# EEZ_DIB_AFE3_r1B4.net
KiCad netlist of a schematic drawn in EAGLE
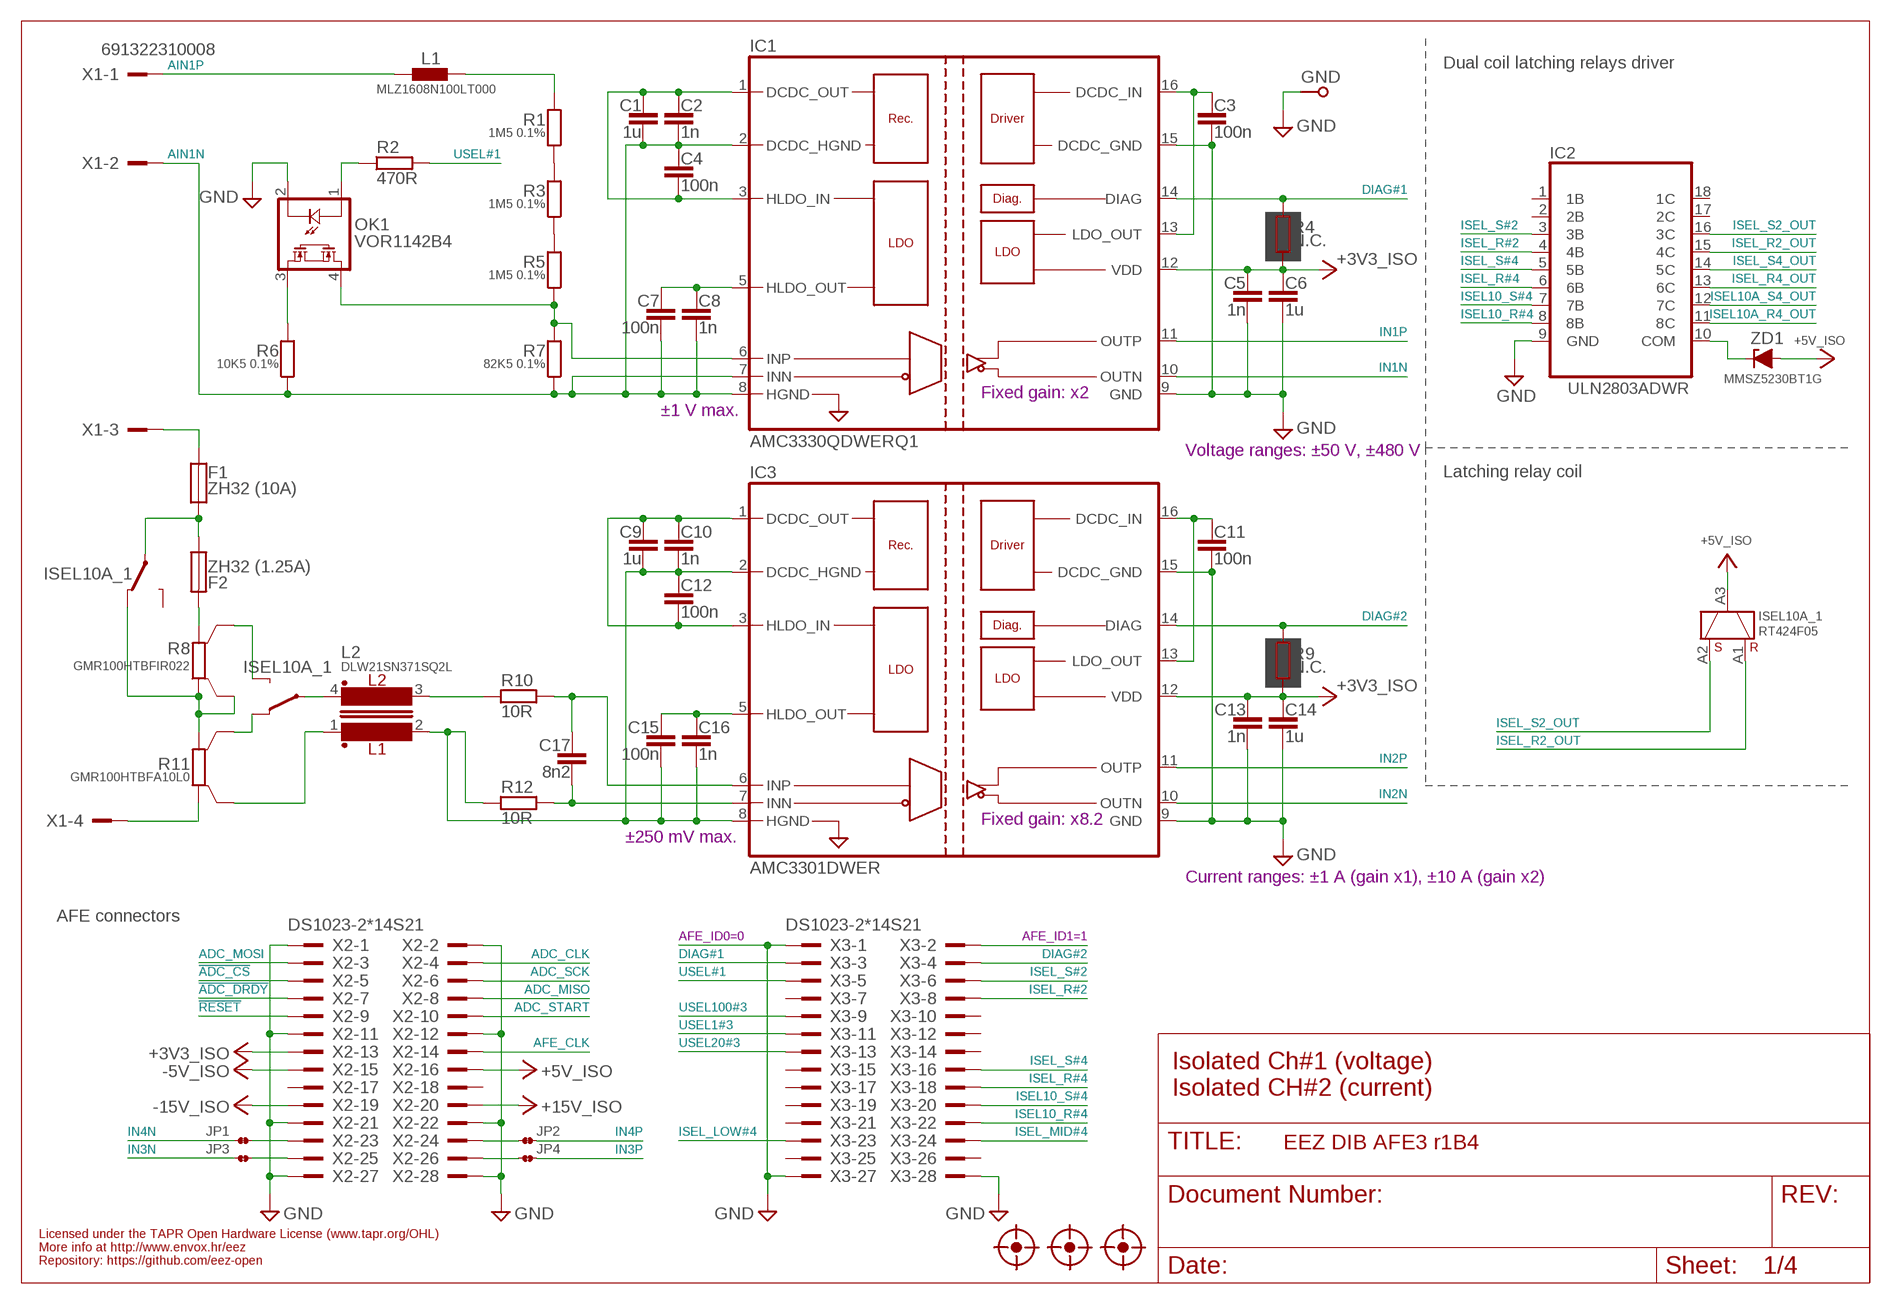
[diagram p0: schematic, sheet 1]
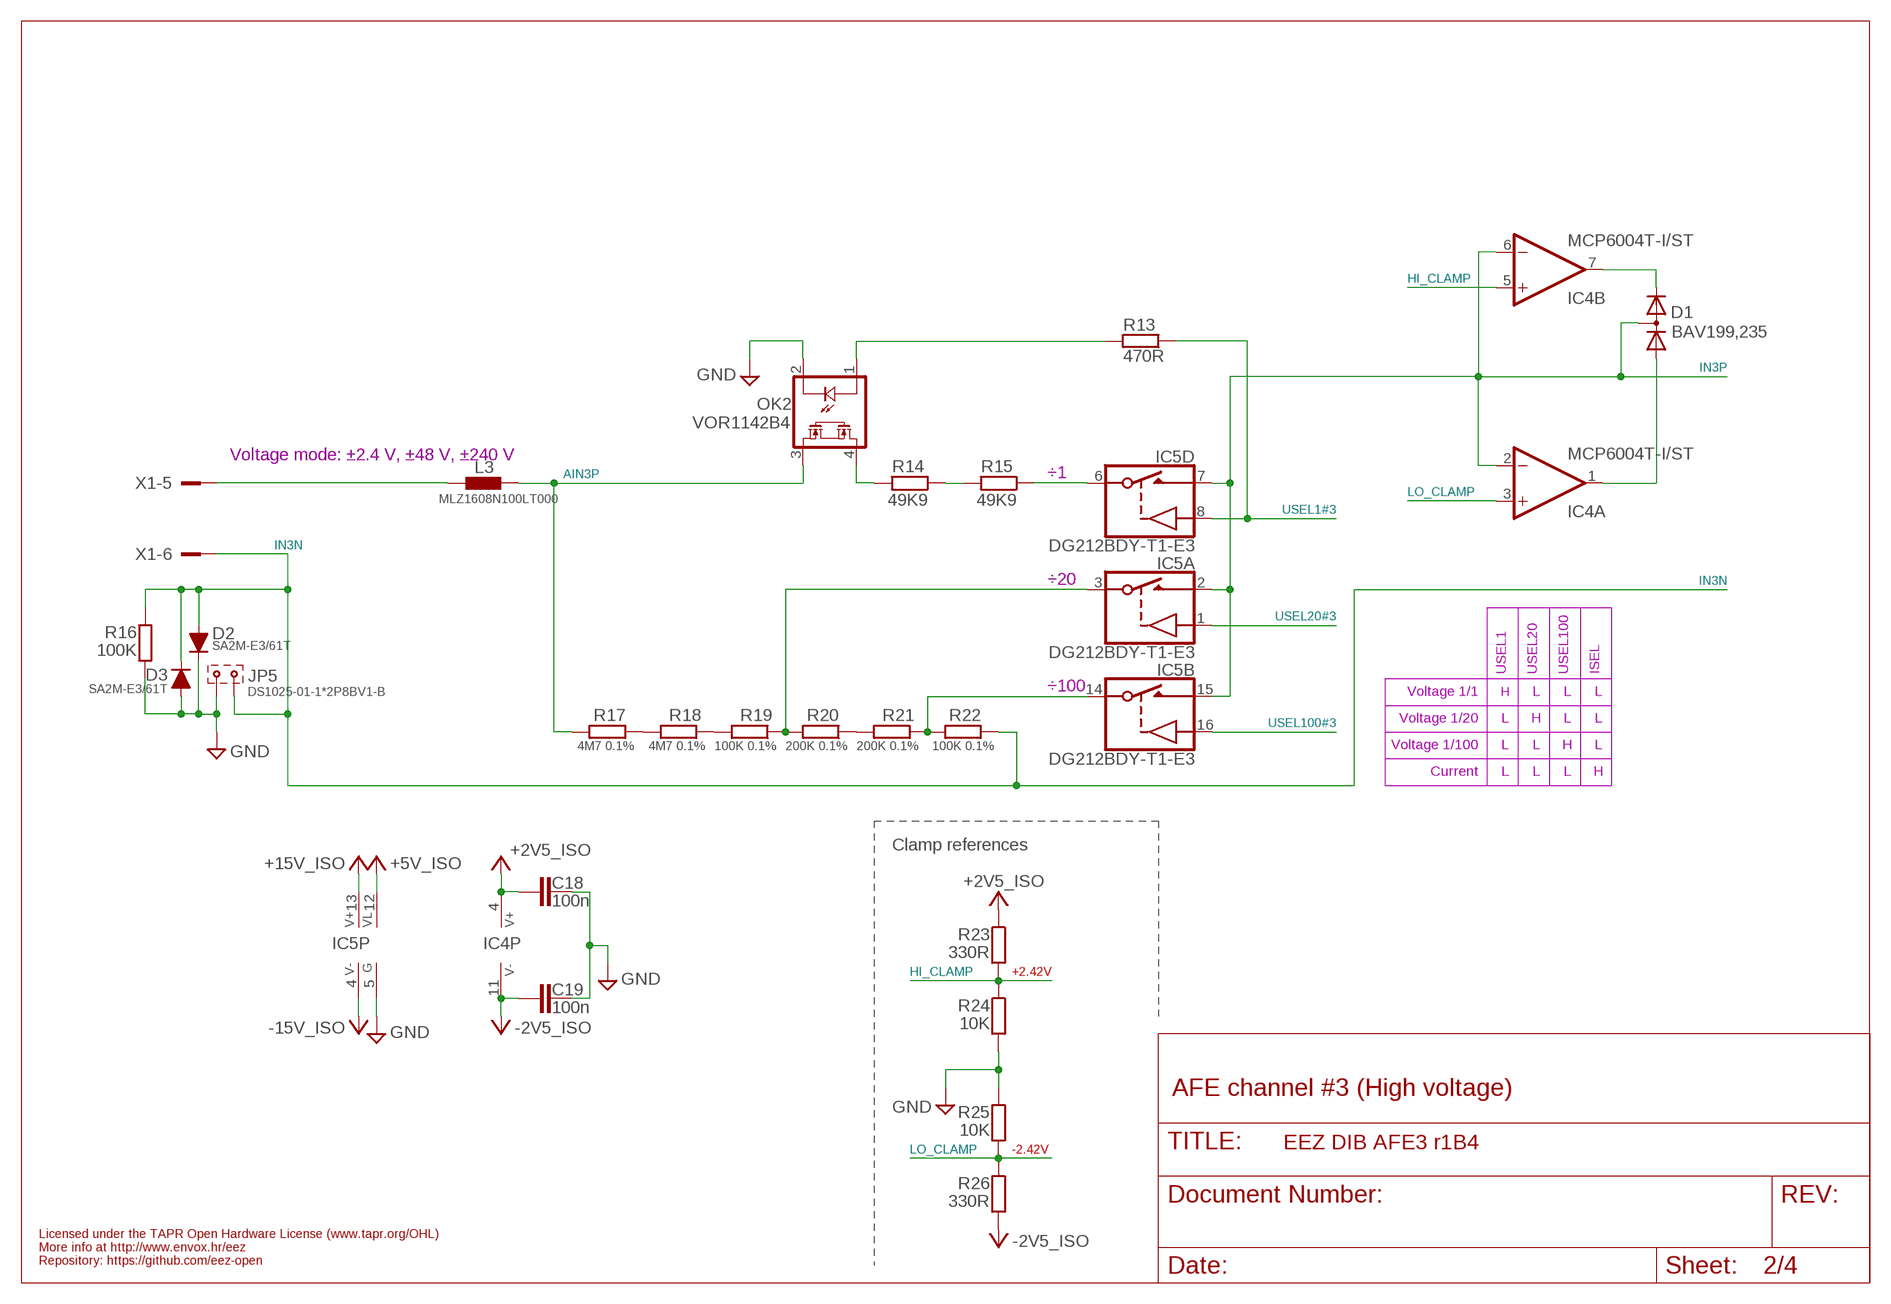
[diagram p1: schematic, sheet 2]
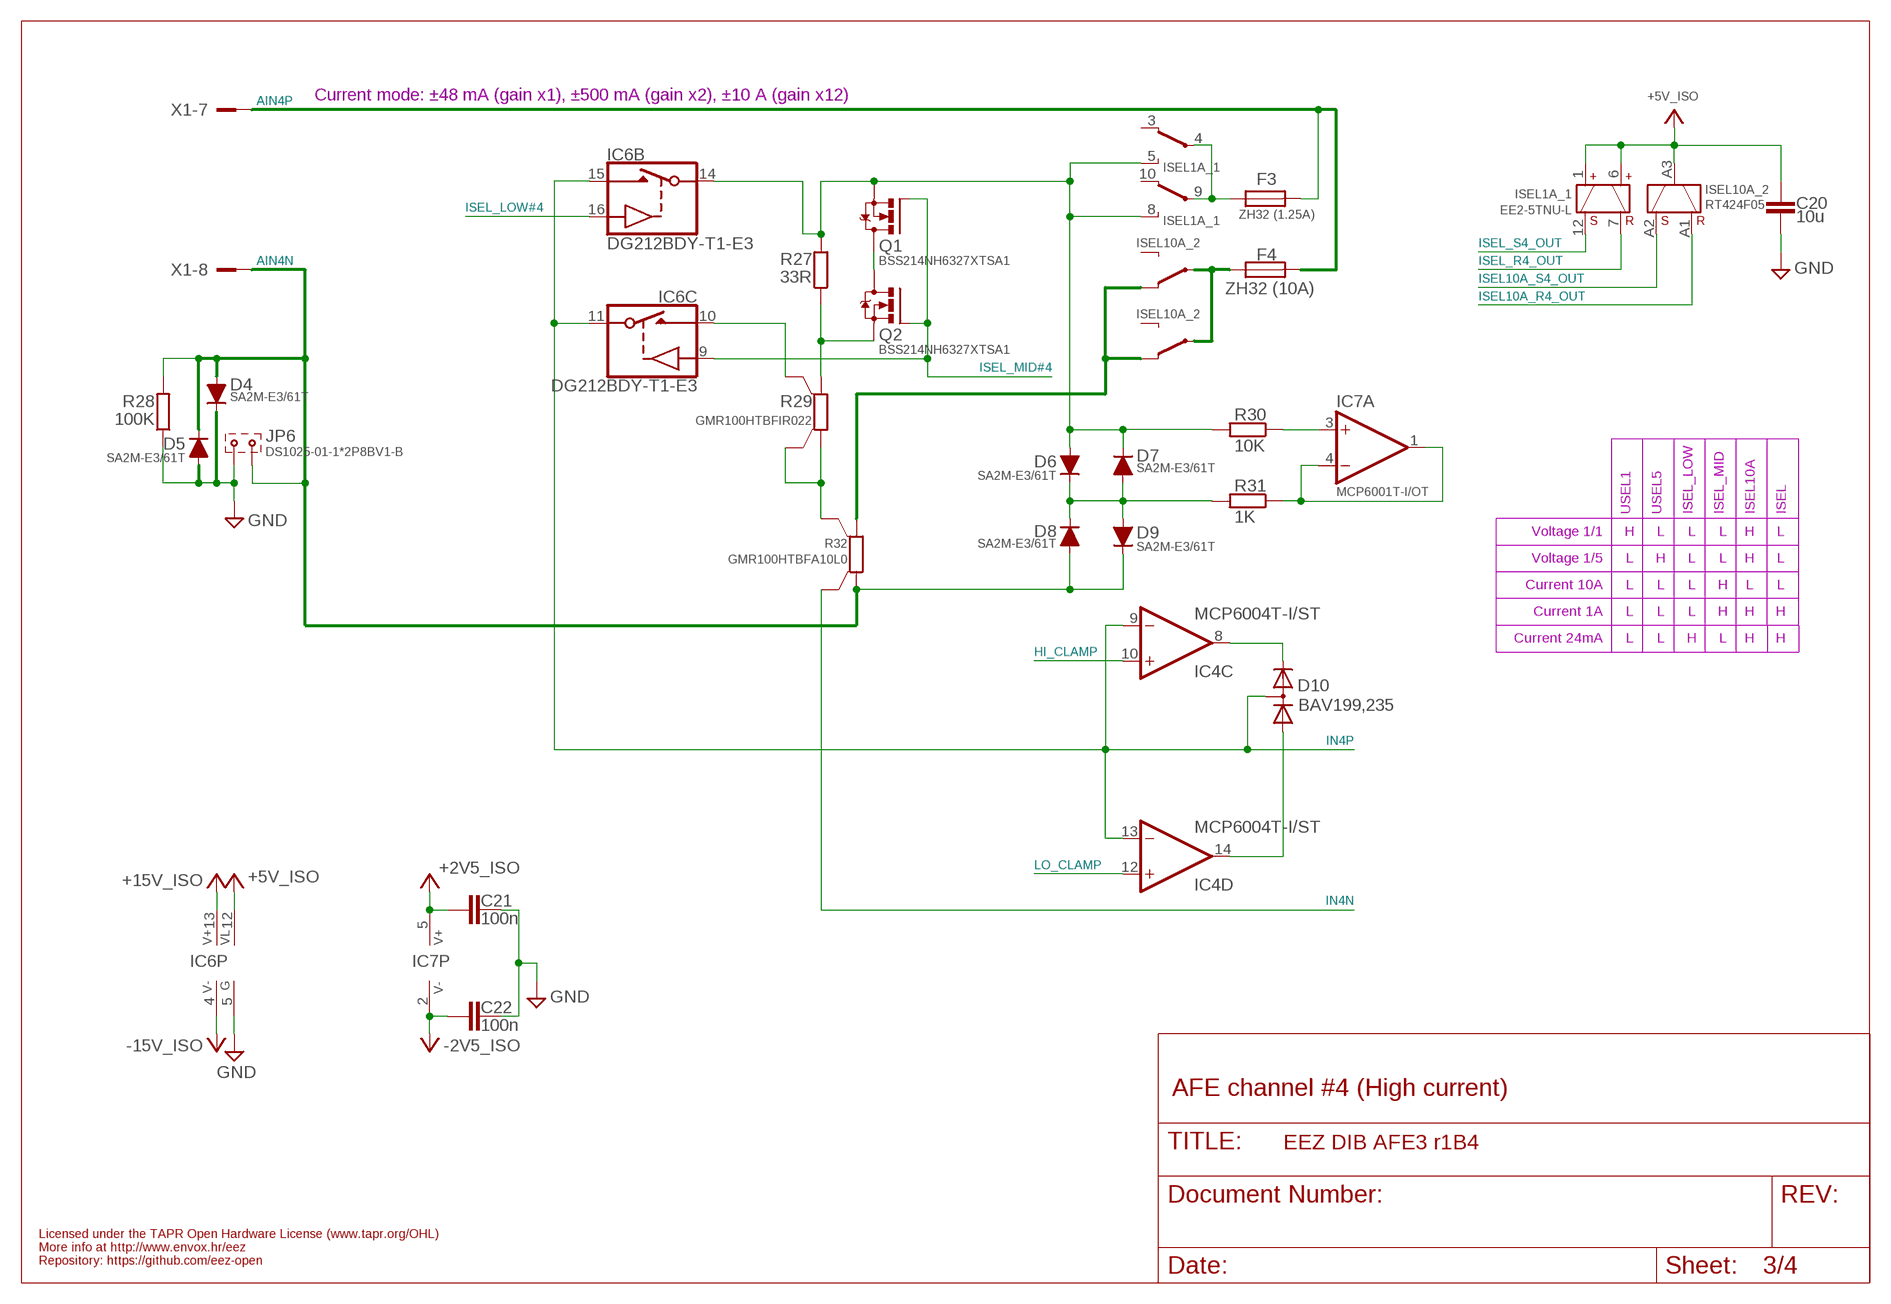
[diagram p2: schematic, sheet 3]
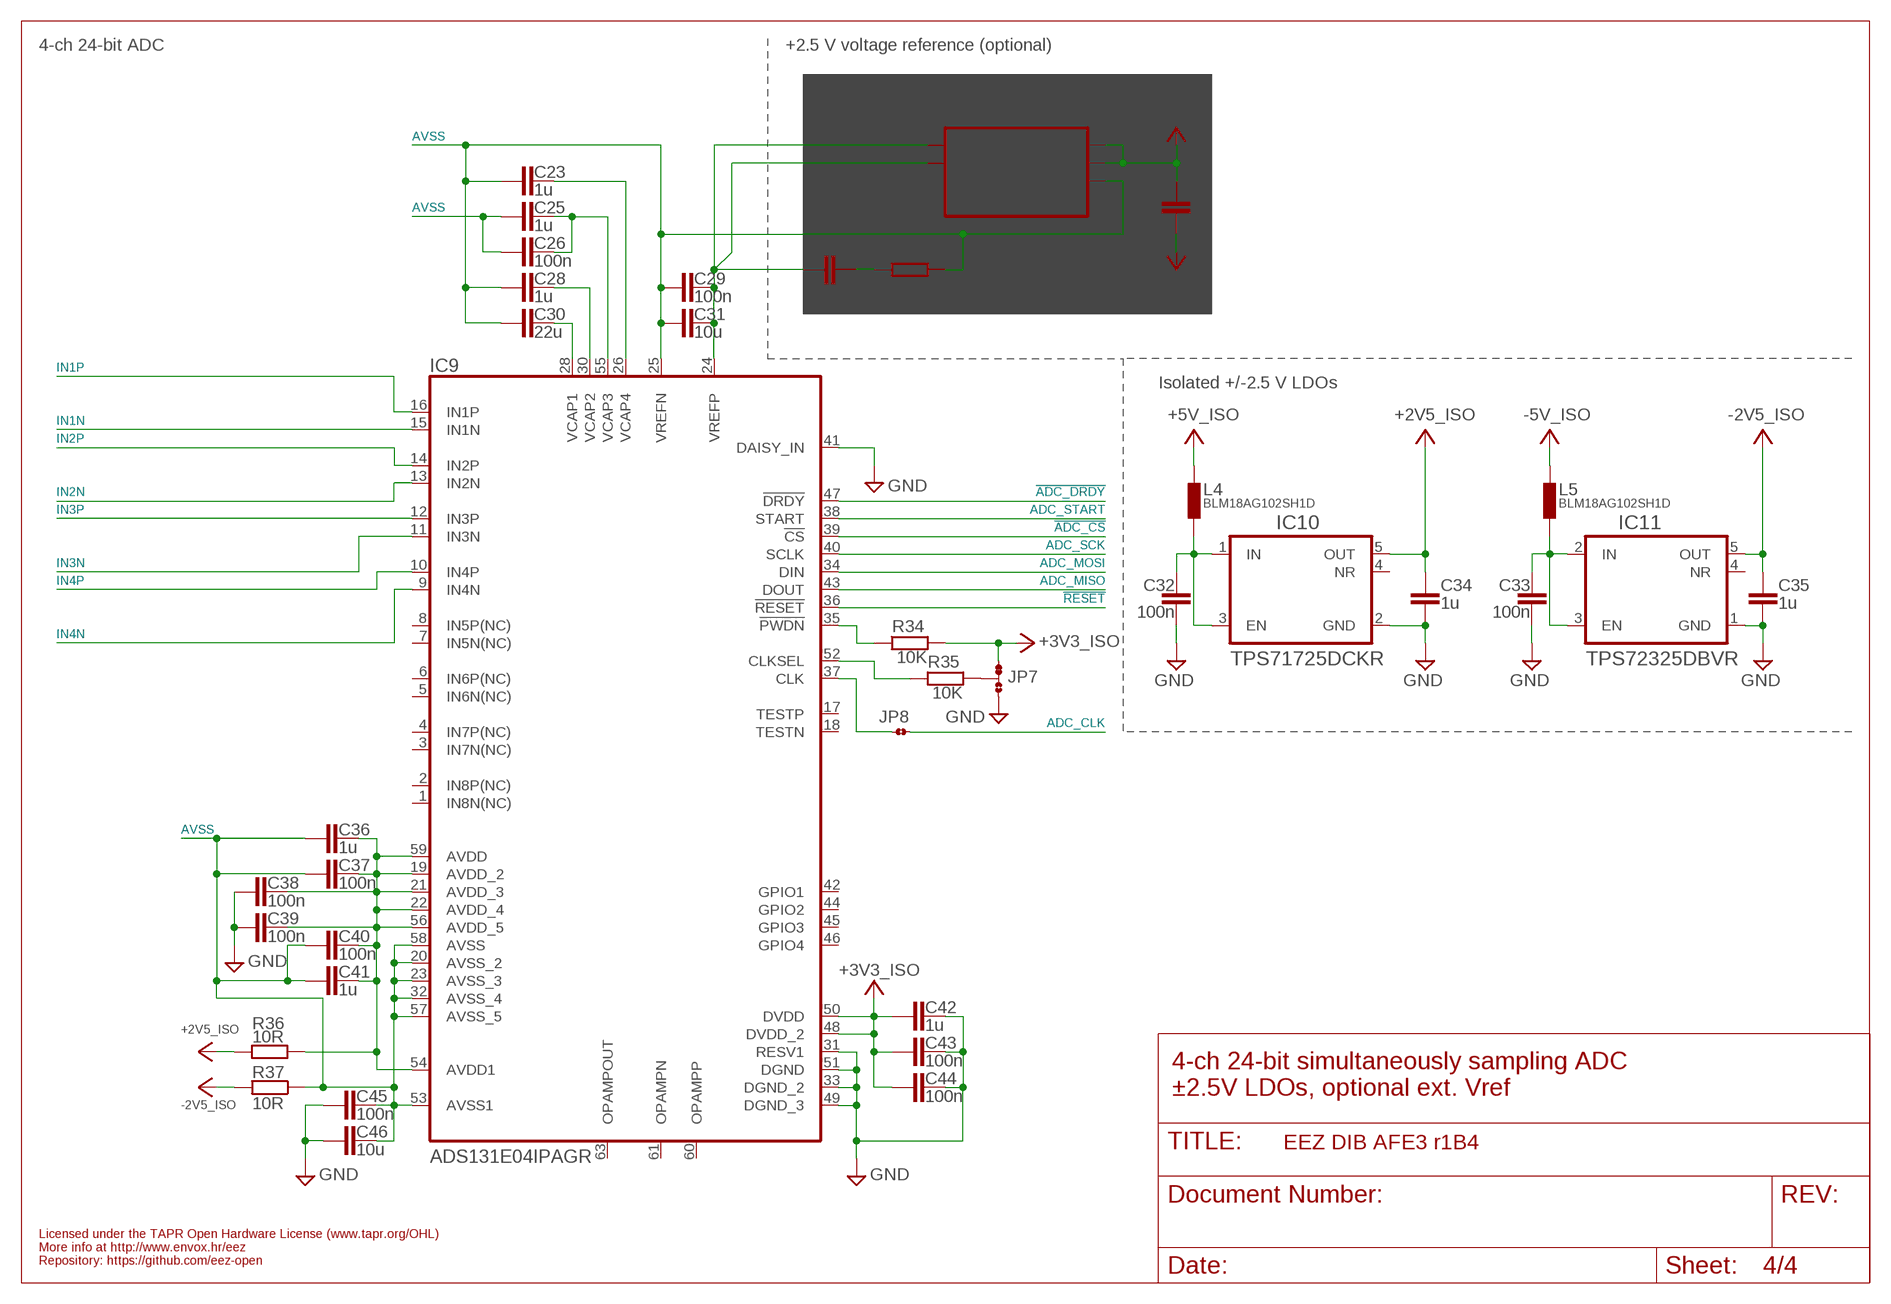
[diagram p3: schematic, sheet 4]

(export (version "E")
  (design (tool "Eeschema 10.0.6"))
  (components
    (comp (ref "C20")
      (value "10u")
      (footprint "eagle-import:C1206")
      (libsource (lib "eagle-import") (part "C-EUC1206"))
    )
    (comp (ref "C21")
      (value "100n")
      (footprint "eagle-import:C0603")
      (libsource (lib "eagle-import") (part "C-EUC0603"))
    )
    (comp (ref "C22")
      (value "100n")
      (footprint "eagle-import:C0603")
      (libsource (lib "eagle-import") (part "C-EUC0603"))
    )
    (comp (ref "D4")
      (value "SA2M-E3/61T")
      (footprint "eagle-import:SMA_NARROW")
      (libsource (lib "eagle-import") (part "DIODE_SMA-NARROW"))
    )
    (comp (ref "D5")
      (value "SA2M-E3/61T")
      (footprint "eagle-import:SMA_NARROW")
      (libsource (lib "eagle-import") (part "DIODE_SMA-NARROW"))
    )
    (comp (ref "D6")
      (value "SA2M-E3/61T")
      (footprint "eagle-import:SMA_NARROW")
      (libsource (lib "eagle-import") (part "DIODE_SMA-NARROW"))
    )
    (comp (ref "D7")
      (value "SA2M-E3/61T")
      (footprint "eagle-import:SMA_NARROW")
      (libsource (lib "eagle-import") (part "DIODE_SMA-NARROW"))
    )
    (comp (ref "D8")
      (value "SA2M-E3/61T")
      (footprint "eagle-import:SMA_NARROW")
      (libsource (lib "eagle-import") (part "DIODE_SMA-NARROW"))
    )
    (comp (ref "D9")
      (value "SA2M-E3/61T")
      (footprint "eagle-import:SMA_NARROW")
      (libsource (lib "eagle-import") (part "DIODE_SMA-NARROW"))
    )
    (comp (ref "D10")
      (value "BAV199,235")
      (footprint "eagle-import:SOT23")
      (libsource (lib "eagle-import") (part "BAV199"))
    )
    (comp (ref "F3")
      (value "ZH32 (1.25A)")
      (footprint "eagle-import:ZH32")
      (libsource (lib "eagle-import") (part "ZH32"))
    )
    (comp (ref "F4")
      (value "ZH32 (10A)")
      (footprint "eagle-import:ZH32")
      (libsource (lib "eagle-import") (part "ZH32"))
    )
    (comp (ref "IC4")
      (value "MCP6004T-I/ST")
      (footprint "eagle-import:PW(R-PDSO-G14)")
      (libsource (lib "eagle-import") (part "OPA4197PW"))
    )
    (comp (ref "IC6")
      (value "DG212BDY-T1-E3")
      (footprint "eagle-import:SO16")
      (libsource (lib "eagle-import") (part "DG212BDY-T1-E3"))
    )
    (comp (ref "IC7")
      (value "MCP6001T-I/OT")
      (footprint "eagle-import:DBV5")
      (libsource (lib "eagle-import") (part "OPA376AIDBVR"))
    )
    (comp (ref "ISEL1A_1")
      (value "EE2-5TNU-L")
      (footprint "eagle-import:G6SK-2F")
      (libsource (lib "eagle-import") (part "G6SK-2F"))
    )
    (comp (ref "ISEL10A_2")
      (value "RT424F05")
      (footprint "eagle-import:RT424FXX")
      (libsource (lib "eagle-import") (part "RT424FXX"))
    )
    (comp (ref "JP6")
      (value "DS1025-01-1*2P8BV1-B")
      (footprint "eagle-import:2MM-2")
      (libsource (lib "eagle-import") (part "JUMPER-2PIN-2MM"))
    )
    (comp (ref "Q1")
      (value "BSS214NH6327XTSA1")
      (footprint "eagle-import:SOT103P240X110-3N")
      (fields
        (field (name "MPN") "2N7002-7-F")
        (field (name "MPN_1") "2N7002-7-F")
        (field (name "OC_FARNELL") "1713823")
        (field (name "OC_NEWARK") "25R5679")
        (field (name "PACKAGE") "SOT-23-3")
        (field (name "SUPPLIER") "DIODES INC.")
      )
      (libsource (lib "eagle-import") (part "2N7002"))
    )
    (comp (ref "Q2")
      (value "BSS214NH6327XTSA1")
      (footprint "eagle-import:SOT103P240X110-3N")
      (fields (field (name "MPN") "2N7002-7-F"))
      (libsource (lib "eagle-import") (part "2N7002"))
    )
    (comp (ref "R27")
      (value "33R")
      (footprint "eagle-import:R1206")
      (libsource (lib "eagle-import") (part "R-EU_R1206"))
    )
    (comp (ref "R28")
      (value "100K")
      (footprint "eagle-import:R1206")
      (libsource (lib "eagle-import") (part "R-EU_R1206"))
    )
    (comp (ref "R29")
      (value "GMR100HTBFIR022")
      (footprint "eagle-import:R_2512-4WIRE")
      (libsource (lib "eagle-import") (part "R-EU_4WIRE2512"))
    )
    (comp (ref "R30")
      (value "10K")
      (footprint "eagle-import:R0805")
      (libsource (lib "eagle-import") (part "R-EU_R0805"))
    )
    (comp (ref "R31")
      (value "1K")
      (footprint "eagle-import:R0805")
      (libsource (lib "eagle-import") (part "R-EU_R0805"))
    )
    (comp (ref "R32")
      (value "GMR100HTBFA10L0")
      (footprint "eagle-import:R_2512-4WIRE")
      (libsource (lib "eagle-import") (part "R-EU_4WIRE2512"))
    )
    (comp (ref "X1")
      (value "691322310008")
      (footprint "eagle-import:691322310008")
      (libsource (lib "eagle-import") (part "691322310008"))
    )
    (comp (ref "C1")
      (value "1u")
      (footprint "eagle-import:C0603")
      (libsource (lib "eagle-import") (part "C-EUC0603"))
    )
    (comp (ref "C2")
      (value "1n")
      (footprint "eagle-import:C0603")
      (libsource (lib "eagle-import") (part "C-EUC0603"))
    )
    (comp (ref "C3")
      (value "100n")
      (footprint "eagle-import:C0603")
      (libsource (lib "eagle-import") (part "C-EUC0603"))
    )
    (comp (ref "C4")
      (value "100n")
      (footprint "eagle-import:C0603")
      (libsource (lib "eagle-import") (part "C-EUC0603"))
    )
    (comp (ref "C5")
      (value "1n")
      (footprint "eagle-import:C1206")
      (libsource (lib "eagle-import") (part "C-EUC1206"))
    )
    (comp (ref "C6")
      (value "1u")
      (footprint "eagle-import:C1206")
      (libsource (lib "eagle-import") (part "C-EUC1206"))
    )
    (comp (ref "C7")
      (value "100n")
      (footprint "eagle-import:C1206")
      (libsource (lib "eagle-import") (part "C-EUC1206"))
    )
    (comp (ref "C8")
      (value "1n")
      (footprint "eagle-import:C1206")
      (libsource (lib "eagle-import") (part "C-EUC1206"))
    )
    (comp (ref "C9")
      (value "1u")
      (footprint "eagle-import:C0603")
      (libsource (lib "eagle-import") (part "C-EUC0603"))
    )
    (comp (ref "C10")
      (value "1n")
      (footprint "eagle-import:C0603")
      (libsource (lib "eagle-import") (part "C-EUC0603"))
    )
    (comp (ref "C11")
      (value "100n")
      (footprint "eagle-import:C0603")
      (libsource (lib "eagle-import") (part "C-EUC0603"))
    )
    (comp (ref "C12")
      (value "100n")
      (footprint "eagle-import:C0603")
      (libsource (lib "eagle-import") (part "C-EUC0603"))
    )
    (comp (ref "C13")
      (value "1n")
      (footprint "eagle-import:C1206")
      (libsource (lib "eagle-import") (part "C-EUC1206"))
    )
    (comp (ref "C14")
      (value "1u")
      (footprint "eagle-import:C1206")
      (libsource (lib "eagle-import") (part "C-EUC1206"))
    )
    (comp (ref "C15")
      (value "100n")
      (footprint "eagle-import:C1206")
      (libsource (lib "eagle-import") (part "C-EUC1206"))
    )
    (comp (ref "C16")
      (value "1n")
      (footprint "eagle-import:C1206")
      (libsource (lib "eagle-import") (part "C-EUC1206"))
    )
    (comp (ref "C17")
      (value "8n2")
      (footprint "eagle-import:C0603")
      (libsource (lib "eagle-import") (part "C-EUC0603"))
    )
    (comp (ref "F1")
      (value "ZH32 (10A)")
      (footprint "eagle-import:ZH32")
      (libsource (lib "eagle-import") (part "ZH32"))
    )
    (comp (ref "F2")
      (value "ZH32 (1.25A)")
      (footprint "eagle-import:ZH32")
      (libsource (lib "eagle-import") (part "ZH32"))
    )
    (comp (ref "FM1")
      (value "FIDUCIAL_2")
      (footprint "eagle-import:FIDUCIAL_DUAL")
      (libsource (lib "eagle-import") (part "FIDUCIAL_2"))
    )
    (comp (ref "FM2")
      (value "FIDUCIAL_2")
      (footprint "eagle-import:FIDUCIAL_DUAL")
      (libsource (lib "eagle-import") (part "FIDUCIAL_2"))
    )
    (comp (ref "FM3")
      (value "FIDUCIAL_2")
      (footprint "eagle-import:FIDUCIAL_DUAL")
      (libsource (lib "eagle-import") (part "FIDUCIAL_2"))
    )
    (comp (ref "GND")
      (value "PCB_TEST_TABSHIELD")
      (footprint "eagle-import:PCB_SHIELD_TAB")
      (libsource (lib "eagle-import") (part "PCB_TEST_TABSHIELD"))
    )
    (comp (ref "IC1")
      (value "AMC3330QDWERQ1")
      (footprint "eagle-import:DW16")
      (libsource (lib "eagle-import") (part "AMC3301DWER"))
    )
    (comp (ref "IC2")
      (value "ULN2803ADWR")
      (footprint "eagle-import:DW18_TEX-M")
      (libsource (lib "eagle-import") (part "ULN2803ADWR"))
    )
    (comp (ref "IC3")
      (value "AMC3301DWER")
      (footprint "eagle-import:DW16")
      (libsource (lib "eagle-import") (part "AMC3301DWER"))
    )
    (comp (ref "ISEL10A_1")
      (value "RT424F05")
      (footprint "eagle-import:RT424FXX")
      (libsource (lib "eagle-import") (part "RT424FXX"))
    )
    (comp (ref "JP1")
      (value "JP2-NOCUT-0805")
      (footprint "eagle-import:JP2-0805-NOCUT")
      (libsource (lib "eagle-import") (part "JP2-NOCUT-0805"))
    )
    (comp (ref "JP2")
      (value "JP2-NOCUT-0805")
      (footprint "eagle-import:JP2-0805-NOCUT")
      (libsource (lib "eagle-import") (part "JP2-NOCUT-0805"))
    )
    (comp (ref "JP3")
      (value "JP2-NOCUT-0805")
      (footprint "eagle-import:JP2-0805-NOCUT")
      (libsource (lib "eagle-import") (part "JP2-NOCUT-0805"))
    )
    (comp (ref "JP4")
      (value "JP2-NOCUT-0805")
      (footprint "eagle-import:JP2-0805-NOCUT")
      (libsource (lib "eagle-import") (part "JP2-NOCUT-0805"))
    )
    (comp (ref "L1")
      (value "MLZ1608N100LT000")
      (footprint "eagle-import:BEAD0603")
      (libsource (lib "eagle-import") (part "FERRITE_BEAD0603"))
    )
    (comp (ref "L2")
      (value "DLW21SN371SQ2L")
      (footprint "eagle-import:MURATA_DLW21S")
      (libsource (lib "eagle-import") (part "DLW21S"))
    )
    (comp (ref "OK1")
      (value "VOR1142B4")
      (footprint "eagle-import:DIL4-SMD")
      (libsource (lib "eagle-import") (part "VOR1142B4"))
    )
    (comp (ref "R1")
      (value "1M5 0.1%")
      (footprint "eagle-import:R1206")
      (libsource (lib "eagle-import") (part "R-EU_R1206"))
    )
    (comp (ref "R2")
      (value "470R")
      (footprint "eagle-import:R0805")
      (libsource (lib "eagle-import") (part "R-EU_R0805"))
    )
    (comp (ref "R3")
      (value "1M5 0.1%")
      (footprint "eagle-import:R1206")
      (libsource (lib "eagle-import") (part "R-EU_R1206"))
    )
    (comp (ref "R4")
      (value "N.C.")
      (footprint "eagle-import:R0805")
      (libsource (lib "eagle-import") (part "R-EU_R0805"))
    )
    (comp (ref "R5")
      (value "1M5 0.1%")
      (footprint "eagle-import:R1206")
      (libsource (lib "eagle-import") (part "R-EU_R1206"))
    )
    (comp (ref "R6")
      (value "10K5 0.1%")
      (footprint "eagle-import:R1206")
      (libsource (lib "eagle-import") (part "R-EU_R1206"))
    )
    (comp (ref "R7")
      (value "82K5 0.1%")
      (footprint "eagle-import:R1206")
      (libsource (lib "eagle-import") (part "R-EU_R1206"))
    )
    (comp (ref "R8")
      (value "GMR100HTBFIR022")
      (footprint "eagle-import:R_2512-4WIRE")
      (libsource (lib "eagle-import") (part "R-EU_4WIRE2512"))
    )
    (comp (ref "R9")
      (value "N.C.")
      (footprint "eagle-import:R0805")
      (libsource (lib "eagle-import") (part "R-EU_R0805"))
    )
    (comp (ref "R10")
      (value "10R")
      (footprint "eagle-import:R0805")
      (libsource (lib "eagle-import") (part "R-EU_R0805"))
    )
    (comp (ref "R11")
      (value "GMR100HTBFA10L0")
      (footprint "eagle-import:R_2512-4WIRE")
      (libsource (lib "eagle-import") (part "R-EU_4WIRE2512"))
    )
    (comp (ref "R12")
      (value "10R")
      (footprint "eagle-import:R0805")
      (libsource (lib "eagle-import") (part "R-EU_R0805"))
    )
    (comp (ref "X2")
      (value "DS1023-2*14S21")
      (footprint "eagle-import:TSW-114-07-F-D")
      (libsource (lib "eagle-import") (part "TSW-114-07-F-D"))
    )
    (comp (ref "X3")
      (value "DS1023-2*14S21")
      (footprint "eagle-import:TSW-114-07-F-D")
      (libsource (lib "eagle-import") (part "TSW-114-07-F-D"))
    )
    (comp (ref "ZD1")
      (value "MMSZ5230BT1G")
      (footprint "eagle-import:SOD123")
      (libsource (lib "eagle-import") (part "ZENER-DIODESOD123"))
    )
    (comp (ref "C23")
      (value "1u")
      (footprint "eagle-import:C0805")
      (libsource (lib "eagle-import") (part "C-EUC0805"))
    )
    (comp (ref "C24")
      (value "N.C.")
      (footprint "eagle-import:C1206")
      (libsource (lib "eagle-import") (part "C-EUC1206"))
    )
    (comp (ref "C25")
      (value "1u")
      (footprint "eagle-import:C0805")
      (libsource (lib "eagle-import") (part "C-EUC0805"))
    )
    (comp (ref "C26")
      (value "100n")
      (footprint "eagle-import:C0603")
      (libsource (lib "eagle-import") (part "C-EUC0603"))
    )
    (comp (ref "C27")
      (value "N.C.")
      (footprint "eagle-import:C1206")
      (libsource (lib "eagle-import") (part "C-EUC1206"))
    )
    (comp (ref "C28")
      (value "1u")
      (footprint "eagle-import:C0805")
      (libsource (lib "eagle-import") (part "C-EUC0805"))
    )
    (comp (ref "C29")
      (value "100n")
      (footprint "eagle-import:C0603")
      (libsource (lib "eagle-import") (part "C-EUC0603"))
    )
    (comp (ref "C30")
      (value "22u")
      (footprint "eagle-import:C1206")
      (libsource (lib "eagle-import") (part "C-EUC1206"))
    )
    (comp (ref "C31")
      (value "10u")
      (footprint "eagle-import:C1206")
      (libsource (lib "eagle-import") (part "C-EUC1206"))
    )
    (comp (ref "C32")
      (value "100n")
      (footprint "eagle-import:C0603")
      (libsource (lib "eagle-import") (part "C-EUC0603"))
    )
    (comp (ref "C33")
      (value "100n")
      (footprint "eagle-import:C0603")
      (libsource (lib "eagle-import") (part "C-EUC0603"))
    )
    (comp (ref "C34")
      (value "1u")
      (footprint "eagle-import:C0805")
      (libsource (lib "eagle-import") (part "C-EUC0805"))
    )
    (comp (ref "C35")
      (value "1u")
      (footprint "eagle-import:C0805")
      (libsource (lib "eagle-import") (part "C-EUC0805"))
    )
    (comp (ref "C36")
      (value "1u")
      (footprint "eagle-import:C0805")
      (libsource (lib "eagle-import") (part "C-EUC0805"))
    )
    (comp (ref "C37")
      (value "100n")
      (footprint "eagle-import:C0603")
      (libsource (lib "eagle-import") (part "C-EUC0603"))
    )
    (comp (ref "C38")
      (value "100n")
      (footprint "eagle-import:C0603")
      (libsource (lib "eagle-import") (part "C-EUC0603"))
    )
    (comp (ref "C39")
      (value "100n")
      (footprint "eagle-import:C0603")
      (libsource (lib "eagle-import") (part "C-EUC0603"))
    )
    (comp (ref "C40")
      (value "100n")
      (footprint "eagle-import:C0603")
      (libsource (lib "eagle-import") (part "C-EUC0603"))
    )
    (comp (ref "C41")
      (value "1u")
      (footprint "eagle-import:C0805")
      (libsource (lib "eagle-import") (part "C-EUC0805"))
    )
    (comp (ref "C42")
      (value "1u")
      (footprint "eagle-import:C0805")
      (libsource (lib "eagle-import") (part "C-EUC0805"))
    )
    (comp (ref "C43")
      (value "100n")
      (footprint "eagle-import:C0603")
      (libsource (lib "eagle-import") (part "C-EUC0603"))
    )
    (comp (ref "C44")
      (value "100n")
      (footprint "eagle-import:C0603")
      (libsource (lib "eagle-import") (part "C-EUC0603"))
    )
    (comp (ref "C45")
      (value "100n")
      (footprint "eagle-import:C0603")
      (libsource (lib "eagle-import") (part "C-EUC0603"))
    )
    (comp (ref "C46")
      (value "10u")
      (footprint "eagle-import:C1206")
      (libsource (lib "eagle-import") (part "C-EUC1206"))
    )
    (comp (ref "IC8")
      (value "N.C.")
      (footprint "eagle-import:MSOP-8_MS_LIT")
      (libsource (lib "eagle-import") (part "LTC6655BHMS8"))
    )
    (comp (ref "IC9")
      (value "ADS131E04IPAGR")
      (footprint "eagle-import:PAG64")
      (libsource (lib "eagle-import") (part "ADS131E0XIPAG"))
    )
    (comp (ref "IC10")
      (value "TPS71725DCKR")
      (footprint "eagle-import:DCK5")
      (libsource (lib "eagle-import") (part "TPS71725DCKR"))
    )
    (comp (ref "IC11")
      (value "TPS72325DBVR")
      (footprint "eagle-import:DBV5")
      (libsource (lib "eagle-import") (part "TPS72325DBVR"))
    )
    (comp (ref "JP7")
      (value "JP3-CUT-0805-ROTATED")
      (footprint "eagle-import:JP3-0805-CUT2")
      (libsource (lib "eagle-import") (part "JP3-CUT-0805-ROTATED"))
    )
    (comp (ref "JP8")
      (value "JP2-CUT-0805")
      (footprint "eagle-import:R_0805")
      (libsource (lib "eagle-import") (part "JP2-CUT-0805"))
    )
    (comp (ref "L4")
      (value "BLM18AG102SH1D")
      (footprint "eagle-import:BEAD0603")
      (libsource (lib "eagle-import") (part "FERRITE_BEAD0603"))
    )
    (comp (ref "L5")
      (value "BLM18AG102SH1D")
      (footprint "eagle-import:BEAD0603")
      (libsource (lib "eagle-import") (part "FERRITE_BEAD0603"))
    )
    (comp (ref "R33")
      (value "N.C.")
      (footprint "eagle-import:R0805")
      (libsource (lib "eagle-import") (part "R-EU_R0805"))
    )
    (comp (ref "R34")
      (value "10K")
      (footprint "eagle-import:R0805")
      (libsource (lib "eagle-import") (part "R-EU_R0805"))
    )
    (comp (ref "R35")
      (value "10K")
      (footprint "eagle-import:R0805")
      (libsource (lib "eagle-import") (part "R-EU_R0805"))
    )
    (comp (ref "R36")
      (value "10R")
      (footprint "eagle-import:R0805")
      (libsource (lib "eagle-import") (part "R-EU_R0805"))
    )
    (comp (ref "R37")
      (value "10R")
      (footprint "eagle-import:R0805")
      (libsource (lib "eagle-import") (part "R-EU_R0805"))
    )
    (comp (ref "C18")
      (value "100n")
      (footprint "eagle-import:C0603")
      (libsource (lib "eagle-import") (part "C-EUC0603"))
    )
    (comp (ref "C19")
      (value "100n")
      (footprint "eagle-import:C0603")
      (libsource (lib "eagle-import") (part "C-EUC0603"))
    )
    (comp (ref "D1")
      (value "BAV199,235")
      (footprint "eagle-import:SOT23")
      (libsource (lib "eagle-import") (part "BAV199"))
    )
    (comp (ref "D2")
      (value "SA2M-E3/61T")
      (footprint "eagle-import:SMA_NARROW")
      (libsource (lib "eagle-import") (part "DIODE_SMA-NARROW"))
    )
    (comp (ref "D3")
      (value "SA2M-E3/61T")
      (footprint "eagle-import:SMA_NARROW")
      (libsource (lib "eagle-import") (part "DIODE_SMA-NARROW"))
    )
    (comp (ref "IC5")
      (value "DG212BDY-T1-E3")
      (footprint "eagle-import:SO16")
      (libsource (lib "eagle-import") (part "DG212BDY-T1-E3"))
    )
    (comp (ref "JP5")
      (value "DS1025-01-1*2P8BV1-B")
      (footprint "eagle-import:2MM-2")
      (libsource (lib "eagle-import") (part "JUMPER-2PIN-2MM"))
    )
    (comp (ref "L3")
      (value "MLZ1608N100LT000")
      (footprint "eagle-import:BEAD0603")
      (libsource (lib "eagle-import") (part "FERRITE_BEAD0603"))
    )
    (comp (ref "OK2")
      (value "VOR1142B4")
      (footprint "eagle-import:DIL4-SMD")
      (libsource (lib "eagle-import") (part "VOR1142B4"))
    )
    (comp (ref "R13")
      (value "470R")
      (footprint "eagle-import:R0805")
      (libsource (lib "eagle-import") (part "R-EU_R0805"))
    )
    (comp (ref "R14")
      (value "49K9")
      (footprint "eagle-import:R1206")
      (libsource (lib "eagle-import") (part "R-EU_R1206"))
    )
    (comp (ref "R15")
      (value "49K9")
      (footprint "eagle-import:R1206")
      (libsource (lib "eagle-import") (part "R-EU_R1206"))
    )
    (comp (ref "R16")
      (value "100K")
      (footprint "eagle-import:R1206")
      (libsource (lib "eagle-import") (part "R-EU_R1206"))
    )
    (comp (ref "R17")
      (value "4M7 0.1%")
      (footprint "eagle-import:R1206")
      (libsource (lib "eagle-import") (part "R-EU_R1206"))
    )
    (comp (ref "R18")
      (value "4M7 0.1%")
      (footprint "eagle-import:R1206")
      (libsource (lib "eagle-import") (part "R-EU_R1206"))
    )
    (comp (ref "R19")
      (value "100K 0.1%")
      (footprint "eagle-import:R1206")
      (libsource (lib "eagle-import") (part "R-EU_R1206"))
    )
    (comp (ref "R20")
      (value "200K 0.1%")
      (footprint "eagle-import:R1206")
      (libsource (lib "eagle-import") (part "R-EU_R1206"))
    )
    (comp (ref "R21")
      (value "200K 0.1%")
      (footprint "eagle-import:R1206")
      (libsource (lib "eagle-import") (part "R-EU_R1206"))
    )
    (comp (ref "R22")
      (value "100K 0.1%")
      (footprint "eagle-import:R1206")
      (libsource (lib "eagle-import") (part "R-EU_R1206"))
    )
    (comp (ref "R23")
      (value "330R")
      (footprint "eagle-import:R0805")
      (libsource (lib "eagle-import") (part "R-EU_R0805"))
    )
    (comp (ref "R24")
      (value "10K")
      (footprint "eagle-import:R0805")
      (libsource (lib "eagle-import") (part "R-EU_R0805"))
    )
    (comp (ref "R25")
      (value "10K")
      (footprint "eagle-import:R0805")
      (libsource (lib "eagle-import") (part "R-EU_R0805"))
    )
    (comp (ref "R26")
      (value "330R")
      (footprint "eagle-import:R0805")
      (libsource (lib "eagle-import") (part "R-EU_R0805"))
    )
  )
  (nets
    (net (code "1") (name "+2V5_ISO") (class "Default")
      (node (ref "C18") (pin "2") (pinfunction "2_2") (pintype "passive"))
      (node (ref "C21") (pin "2") (pinfunction "2_2") (pintype "passive"))
      (node (ref "C34") (pin "2") (pinfunction "2_2") (pintype "passive"))
      (node (ref "IC10") (pin "5") (pinfunction "OUT_5") (pintype "passive"))
      (node (ref "IC4") (pin "4") (pinfunction "V+_4") (pintype "power_in"))
      (node (ref "IC7") (pin "5") (pinfunction "V+_5") (pintype "power_in"))
      (node (ref "R23") (pin "1") (pinfunction "1_1") (pintype "passive"))
      (node (ref "R36") (pin "1") (pinfunction "1_1") (pintype "passive"))
    )
    (net (code "2") (name "+3V3_ISO") (class "Default")
      (node (ref "C13") (pin "1") (pinfunction "1_1") (pintype "passive"))
      (node (ref "C14") (pin "1") (pinfunction "1_1") (pintype "passive"))
      (node (ref "C42") (pin "1") (pinfunction "1_1") (pintype "passive"))
      (node (ref "C43") (pin "2") (pinfunction "2_2") (pintype "passive"))
      (node (ref "C44") (pin "2") (pinfunction "2_2") (pintype "passive"))
      (node (ref "C5") (pin "1") (pinfunction "1_1") (pintype "passive"))
      (node (ref "C6") (pin "1") (pinfunction "1_1") (pintype "passive"))
      (node (ref "IC1") (pin "12") (pinfunction "VDD_12") (pintype "passive"))
      (node (ref "IC3") (pin "12") (pinfunction "VDD_12") (pintype "passive"))
      (node (ref "IC9") (pin "48") (pinfunction "DVDD_2_48") (pintype "power_in"))
      (node (ref "IC9") (pin "50") (pinfunction "DVDD_50") (pintype "power_in"))
      (node (ref "JP7") (pin "NC") (pinfunction "NC_NC") (pintype "passive"))
      (node (ref "R34") (pin "2") (pinfunction "2_2") (pintype "passive"))
      (node (ref "R4") (pin "2") (pinfunction "2_2") (pintype "passive"))
      (node (ref "R9") (pin "2") (pinfunction "2_2") (pintype "passive"))
      (node (ref "X2") (pin "13") (pinfunction "1_13") (pintype "passive"))
    )
    (net (code "3") (name "+5V_ISO") (class "Default")
      (node (ref "C20") (pin "1") (pinfunction "1_1") (pintype "passive"))
      (node (ref "C24") (pin "1") (pinfunction "1_1") (pintype "passive"))
      (node (ref "IC5") (pin "12") (pinfunction "VL_12") (pintype "power_in"))
      (node (ref "IC6") (pin "12") (pinfunction "VL_12") (pintype "power_in"))
      (node (ref "IC8") (pin "1") (pinfunction "~{SHDN}_1") (pintype "input"))
      (node (ref "IC8") (pin "2") (pinfunction "VIN_2") (pintype "input"))
      (node (ref "ISEL10A_1") (pin "A3") (pinfunction "COM_A3") (pintype "passive"))
      (node (ref "ISEL10A_2") (pin "A3") (pinfunction "COM_A3") (pintype "passive"))
      (node (ref "ISEL1A_1") (pin "1") (pinfunction "S+_1") (pintype "passive"))
      (node (ref "ISEL1A_1") (pin "6") (pinfunction "R+_6") (pintype "passive"))
      (node (ref "L4") (pin "P$2") (pinfunction "2_P$2") (pintype "passive"))
      (node (ref "X2") (pin "16") (pinfunction "1_16") (pintype "passive"))
      (node (ref "ZD1") (pin "A") (pinfunction "A_A") (pintype "passive"))
    )
    (net (code "4") (name "+15V_ISO") (class "Default")
      (node (ref "IC5") (pin "13") (pinfunction "V+_13") (pintype "power_in"))
      (node (ref "IC6") (pin "13") (pinfunction "V+_13") (pintype "power_in"))
      (node (ref "X2") (pin "20") (pinfunction "1_20") (pintype "passive"))
    )
    (net (code "5") (name "-2V5_ISO") (class "Default")
      (node (ref "C19") (pin "2") (pinfunction "2_2") (pintype "passive"))
      (node (ref "C22") (pin "2") (pinfunction "2_2") (pintype "passive"))
      (node (ref "C24") (pin "2") (pinfunction "2_2") (pintype "passive"))
      (node (ref "C35") (pin "2") (pinfunction "2_2") (pintype "passive"))
      (node (ref "IC11") (pin "5") (pinfunction "OUT_5") (pintype "passive"))
      (node (ref "IC4") (pin "11") (pinfunction "V-_11") (pintype "power_in"))
      (node (ref "IC7") (pin "2") (pinfunction "V-_2") (pintype "power_in"))
      (node (ref "R26") (pin "2") (pinfunction "2_2") (pintype "passive"))
      (node (ref "R37") (pin "2") (pinfunction "2_2") (pintype "passive"))
    )
    (net (code "6") (name "-5V_ISO") (class "Default")
      (node (ref "L5") (pin "P$2") (pinfunction "2_P$2") (pintype "passive"))
      (node (ref "X2") (pin "15") (pinfunction "1_15") (pintype "passive"))
    )
    (net (code "7") (name "-15V_ISO") (class "Default")
      (node (ref "IC5") (pin "4") (pinfunction "V-_4") (pintype "power_in"))
      (node (ref "IC6") (pin "4") (pinfunction "V-_4") (pintype "power_in"))
      (node (ref "X2") (pin "19") (pinfunction "1_19") (pintype "passive"))
    )
    (net (code "8") (name "ADC_CLK") (class "Default")
      (node (ref "JP8") (pin "1") (pinfunction "1_1") (pintype "passive"))
      (node (ref "X2") (pin "4") (pinfunction "1_4") (pintype "passive"))
    )
    (net (code "9") (name "ADC_MISO") (class "Default")
      (node (ref "IC9") (pin "43") (pinfunction "DOUT_43") (pintype "output"))
      (node (ref "X2") (pin "8") (pinfunction "1_8") (pintype "passive"))
    )
    (net (code "10") (name "ADC_MOSI") (class "Default")
      (node (ref "IC9") (pin "34") (pinfunction "DIN_34") (pintype "input"))
      (node (ref "X2") (pin "3") (pinfunction "1_3") (pintype "passive"))
    )
    (net (code "11") (name "ADC_SCK") (class "Default")
      (node (ref "IC9") (pin "40") (pinfunction "SCLK_40") (pintype "input"))
      (node (ref "X2") (pin "6") (pinfunction "1_6") (pintype "passive"))
    )
    (net (code "12") (name "ADC_START") (class "Default")
      (node (ref "IC9") (pin "38") (pinfunction "START_38") (pintype "input"))
      (node (ref "X2") (pin "10") (pinfunction "1_10") (pintype "passive"))
    )
    (net (code "13") (name "AFE_CLK") (class "Default")
      (node (ref "X2") (pin "14") (pinfunction "1_14") (pintype "passive"))
    )
    (net (code "14") (name "AIN1N") (class "Default")
      (node (ref "C1") (pin "2") (pinfunction "2_2") (pintype "passive"))
      (node (ref "C2") (pin "2") (pinfunction "2_2") (pintype "passive"))
      (node (ref "C4") (pin "1") (pinfunction "1_1") (pintype "passive"))
      (node (ref "C7") (pin "2") (pinfunction "2_2") (pintype "passive"))
      (node (ref "C8") (pin "2") (pinfunction "2_2") (pintype "passive"))
      (node (ref "IC1") (pin "2") (pinfunction "DCDC_HGND_2") (pintype "passive"))
      (node (ref "IC1") (pin "7") (pinfunction "INN_7") (pintype "input"))
      (node (ref "IC1") (pin "8") (pinfunction "HGND_8") (pintype "passive"))
      (node (ref "R6") (pin "1") (pinfunction "1_1") (pintype "passive"))
      (node (ref "R7") (pin "1") (pinfunction "1_1") (pintype "passive"))
      (node (ref "X1") (pin "2") (pinfunction "1_2") (pintype "passive"))
    )
    (net (code "15") (name "AIN1P") (class "Default")
      (node (ref "L1") (pin "P$2") (pinfunction "2_P$2") (pintype "passive"))
      (node (ref "X1") (pin "1") (pinfunction "1_1") (pintype "passive"))
    )
    (net (code "16") (name "AIN3P") (class "Default")
      (node (ref "L3") (pin "P$1") (pinfunction "1_P$1") (pintype "passive"))
      (node (ref "OK2") (pin "3") (pinfunction "S2_3") (pintype "passive"))
      (node (ref "R17") (pin "2") (pinfunction "2_2") (pintype "passive"))
    )
    (net (code "17") (name "AIN4N") (class "Default")
      (node (ref "D4") (pin "2") (pinfunction "A_2") (pintype "passive"))
      (node (ref "D5") (pin "1") (pinfunction "C_1") (pintype "passive"))
      (node (ref "D8") (pin "2") (pinfunction "A_2") (pintype "passive"))
      (node (ref "D9") (pin "1") (pinfunction "C_1") (pintype "passive"))
      (node (ref "JP6") (pin "1") (pinfunction "1_1") (pintype "passive"))
      (node (ref "R28") (pin "2") (pinfunction "2_2") (pintype "passive"))
      (node (ref "R32") (pin "1") (pinfunction "1_1") (pintype "passive"))
      (node (ref "X1") (pin "8") (pinfunction "1_8") (pintype "passive"))
    )
    (net (code "18") (name "AIN4P") (class "Default")
      (node (ref "F3") (pin "2") (pinfunction "2_2") (pintype "passive"))
      (node (ref "F4") (pin "2") (pinfunction "2_2") (pintype "passive"))
      (node (ref "X1") (pin "7") (pinfunction "1_7") (pintype "passive"))
    )
    (net (code "19") (name "AVSS") (class "Default")
      (node (ref "C23") (pin "1") (pinfunction "1_1") (pintype "passive"))
      (node (ref "C25") (pin "1") (pinfunction "1_1") (pintype "passive"))
      (node (ref "C26") (pin "2") (pinfunction "2_2") (pintype "passive"))
      (node (ref "C28") (pin "1") (pinfunction "1_1") (pintype "passive"))
      (node (ref "C29") (pin "2") (pinfunction "2_2") (pintype "passive"))
      (node (ref "C30") (pin "1") (pinfunction "1_1") (pintype "passive"))
      (node (ref "C31") (pin "2") (pinfunction "2_2") (pintype "passive"))
      (node (ref "C36") (pin "1") (pinfunction "1_1") (pintype "passive"))
      (node (ref "C37") (pin "2") (pinfunction "2_2") (pintype "passive"))
      (node (ref "C40") (pin "2") (pinfunction "2_2") (pintype "passive"))
      (node (ref "C41") (pin "1") (pinfunction "1_1") (pintype "passive"))
      (node (ref "C45") (pin "1") (pinfunction "1_1") (pintype "passive"))
      (node (ref "C46") (pin "1") (pinfunction "1_1") (pintype "passive"))
      (node (ref "IC8") (pin "3") (pinfunction "GND_3") (pintype "power_in"))
      (node (ref "IC8") (pin "4") (pinfunction "GND_4") (pintype "power_in"))
      (node (ref "IC8") (pin "5") (pinfunction "GND_5") (pintype "power_in"))
      (node (ref "IC8") (pin "8") (pinfunction "GND_8") (pintype "power_in"))
      (node (ref "IC9") (pin "20") (pinfunction "AVSS_2_20") (pintype "power_in"))
      (node (ref "IC9") (pin "23") (pinfunction "AVSS_3_23") (pintype "power_in"))
      (node (ref "IC9") (pin "25") (pinfunction "VREFN_25") (pintype "input"))
      (node (ref "IC9") (pin "32") (pinfunction "AVSS_4_32") (pintype "power_in"))
      (node (ref "IC9") (pin "53") (pinfunction "AVSS1_53") (pintype "power_in"))
      (node (ref "IC9") (pin "57") (pinfunction "AVSS_5_57") (pintype "power_in"))
      (node (ref "IC9") (pin "58") (pinfunction "AVSS_58") (pintype "power_in"))
      (node (ref "R33") (pin "2") (pinfunction "2_2") (pintype "passive"))
      (node (ref "R37") (pin "1") (pinfunction "1_1") (pintype "passive"))
    )
    (net (code "20") (name "DIAG#1") (class "Default")
      (node (ref "IC1") (pin "14") (pinfunction "DIAG_14") (pintype "output"))
      (node (ref "R4") (pin "1") (pinfunction "1_1") (pintype "passive"))
      (node (ref "X3") (pin "3") (pinfunction "1_3") (pintype "passive"))
    )
    (net (code "21") (name "DIAG#2") (class "Default")
      (node (ref "IC3") (pin "14") (pinfunction "DIAG_14") (pintype "output"))
      (node (ref "R9") (pin "1") (pinfunction "1_1") (pintype "passive"))
      (node (ref "X3") (pin "4") (pinfunction "1_4") (pintype "passive"))
    )
    (net (code "22") (name "GND") (class "Default")
      (node (ref "C11") (pin "2") (pinfunction "2_2") (pintype "passive"))
      (node (ref "C13") (pin "2") (pinfunction "2_2") (pintype "passive"))
      (node (ref "C14") (pin "2") (pinfunction "2_2") (pintype "passive"))
      (node (ref "C18") (pin "1") (pinfunction "1_1") (pintype "passive"))
      (node (ref "C19") (pin "1") (pinfunction "1_1") (pintype "passive"))
      (node (ref "C20") (pin "2") (pinfunction "2_2") (pintype "passive"))
      (node (ref "C21") (pin "1") (pinfunction "1_1") (pintype "passive"))
      (node (ref "C22") (pin "1") (pinfunction "1_1") (pintype "passive"))
      (node (ref "C3") (pin "2") (pinfunction "2_2") (pintype "passive"))
      (node (ref "C32") (pin "2") (pinfunction "2_2") (pintype "passive"))
      (node (ref "C33") (pin "2") (pinfunction "2_2") (pintype "passive"))
      (node (ref "C34") (pin "1") (pinfunction "1_1") (pintype "passive"))
      (node (ref "C35") (pin "1") (pinfunction "1_1") (pintype "passive"))
      (node (ref "C38") (pin "2") (pinfunction "2_2") (pintype "passive"))
      (node (ref "C39") (pin "2") (pinfunction "2_2") (pintype "passive"))
      (node (ref "C42") (pin "2") (pinfunction "2_2") (pintype "passive"))
      (node (ref "C43") (pin "1") (pinfunction "1_1") (pintype "passive"))
      (node (ref "C44") (pin "1") (pinfunction "1_1") (pintype "passive"))
      (node (ref "C45") (pin "2") (pinfunction "2_2") (pintype "passive"))
      (node (ref "C46") (pin "2") (pinfunction "2_2") (pintype "passive"))
      (node (ref "C5") (pin "2") (pinfunction "2_2") (pintype "passive"))
      (node (ref "C6") (pin "2") (pinfunction "2_2") (pintype "passive"))
      (node (ref "D2") (pin "1") (pinfunction "C_1") (pintype "passive"))
      (node (ref "D3") (pin "2") (pinfunction "A_2") (pintype "passive"))
      (node (ref "D4") (pin "1") (pinfunction "C_1") (pintype "passive"))
      (node (ref "D5") (pin "2") (pinfunction "A_2") (pintype "passive"))
      (node (ref "GND") (pin "1") (pinfunction "P$1_1") (pintype "bidirectional"))
      (node (ref "IC1") (pin "15") (pinfunction "DCDC_GND_15") (pintype "passive"))
      (node (ref "IC1") (pin "9") (pinfunction "GND_9") (pintype "passive"))
      (node (ref "IC10") (pin "2") (pinfunction "GND_2") (pintype "passive"))
      (node (ref "IC11") (pin "1") (pinfunction "GND_1") (pintype "passive"))
      (node (ref "IC2") (pin "9") (pinfunction "GND_9") (pintype "input"))
      (node (ref "IC3") (pin "15") (pinfunction "DCDC_GND_15") (pintype "passive"))
      (node (ref "IC3") (pin "9") (pinfunction "GND_9") (pintype "passive"))
      (node (ref "IC5") (pin "5") (pinfunction "GND_5") (pintype "power_in"))
      (node (ref "IC6") (pin "5") (pinfunction "GND_5") (pintype "power_in"))
      (node (ref "IC9") (pin "31") (pinfunction "RESV1_31") (pintype "input"))
      (node (ref "IC9") (pin "33") (pinfunction "DGND_2_33") (pintype "power_in"))
      (node (ref "IC9") (pin "41") (pinfunction "DAISY_IN_41") (pintype "input"))
      (node (ref "IC9") (pin "49") (pinfunction "DGND_3_49") (pintype "power_in"))
      (node (ref "IC9") (pin "51") (pinfunction "DGND_51") (pintype "power_in"))
      (node (ref "JP5") (pin "2") (pinfunction "2_2") (pintype "passive"))
      (node (ref "JP6") (pin "2") (pinfunction "2_2") (pintype "passive"))
      (node (ref "JP7") (pin "NO") (pinfunction "NO_NO") (pintype "passive"))
      (node (ref "OK1") (pin "2") (pinfunction "C_2") (pintype "passive"))
      (node (ref "OK2") (pin "2") (pinfunction "C_2") (pintype "passive"))
      (node (ref "R16") (pin "1") (pinfunction "1_1") (pintype "passive"))
      (node (ref "R24") (pin "2") (pinfunction "2_2") (pintype "passive"))
      (node (ref "R25") (pin "1") (pinfunction "1_1") (pintype "passive"))
      (node (ref "R28") (pin "1") (pinfunction "1_1") (pintype "passive"))
      (node (ref "X2") (pin "1") (pinfunction "1_1") (pintype "passive"))
      (node (ref "X2") (pin "11") (pinfunction "1_11") (pintype "passive"))
      (node (ref "X2") (pin "12") (pinfunction "1_12") (pintype "passive"))
      (node (ref "X2") (pin "2") (pinfunction "1_2") (pintype "passive"))
      (node (ref "X2") (pin "21") (pinfunction "1_21") (pintype "passive"))
      (node (ref "X2") (pin "22") (pinfunction "1_22") (pintype "passive"))
      (node (ref "X2") (pin "27") (pinfunction "1_27") (pintype "passive"))
      (node (ref "X2") (pin "28") (pinfunction "1_28") (pintype "passive"))
      (node (ref "X3") (pin "1") (pinfunction "1_1") (pintype "passive"))
      (node (ref "X3") (pin "27") (pinfunction "1_27") (pintype "passive"))
      (node (ref "X3") (pin "28") (pinfunction "1_28") (pintype "passive"))
    )
    (net (code "23") (name "HI_CLAMP") (class "Default")
      (node (ref "IC4") (pin "10") (pinfunction "+IN_10") (pintype "input"))
      (node (ref "IC4") (pin "5") (pinfunction "+IN_5") (pintype "input"))
      (node (ref "R23") (pin "2") (pinfunction "2_2") (pintype "passive"))
      (node (ref "R24") (pin "1") (pinfunction "1_1") (pintype "passive"))
    )
    (net (code "24") (name "IN1N") (class "Default")
      (node (ref "IC1") (pin "10") (pinfunction "OUTN_10") (pintype "output"))
      (node (ref "IC9") (pin "15") (pinfunction "IN1N_15") (pintype "input"))
    )
    (net (code "25") (name "IN1P") (class "Default")
      (node (ref "IC1") (pin "11") (pinfunction "OUTP_11") (pintype "output"))
      (node (ref "IC9") (pin "16") (pinfunction "IN1P_16") (pintype "input"))
    )
    (net (code "26") (name "IN2N") (class "Default")
      (node (ref "IC3") (pin "10") (pinfunction "OUTN_10") (pintype "output"))
      (node (ref "IC9") (pin "13") (pinfunction "IN2N_13") (pintype "input"))
    )
    (net (code "27") (name "IN2P") (class "Default")
      (node (ref "IC3") (pin "11") (pinfunction "OUTP_11") (pintype "output"))
      (node (ref "IC9") (pin "14") (pinfunction "IN2P_14") (pintype "input"))
    )
    (net (code "28") (name "IN3N") (class "Default")
      (node (ref "D2") (pin "2") (pinfunction "A_2") (pintype "passive"))
      (node (ref "D3") (pin "1") (pinfunction "C_1") (pintype "passive"))
      (node (ref "IC9") (pin "11") (pinfunction "IN3N_11") (pintype "input"))
      (node (ref "JP3") (pin "1") (pinfunction "1_1") (pintype "passive"))
      (node (ref "JP5") (pin "1") (pinfunction "1_1") (pintype "passive"))
      (node (ref "R16") (pin "2") (pinfunction "2_2") (pintype "passive"))
      (node (ref "R22") (pin "1") (pinfunction "1_1") (pintype "passive"))
      (node (ref "X1") (pin "6") (pinfunction "1_6") (pintype "passive"))
    )
    (net (code "29") (name "IN3P") (class "Default")
      (node (ref "D1") (pin "3") (pinfunction "AC_3") (pintype "passive"))
      (node (ref "IC4") (pin "2") (pinfunction "-IN_2") (pintype "input"))
      (node (ref "IC4") (pin "6") (pinfunction "-IN_6") (pintype "input"))
      (node (ref "IC5") (pin "15") (pinfunction "D_15") (pintype "bidirectional"))
      (node (ref "IC5") (pin "2") (pinfunction "D_2") (pintype "bidirectional"))
      (node (ref "IC5") (pin "7") (pinfunction "D_7") (pintype "bidirectional"))
      (node (ref "IC9") (pin "12") (pinfunction "IN3P_12") (pintype "input"))
      (node (ref "JP4") (pin "2") (pinfunction "2_2") (pintype "passive"))
    )
    (net (code "30") (name "IN4N") (class "Default")
      (node (ref "IC9") (pin "9") (pinfunction "IN4N_9") (pintype "input"))
      (node (ref "JP1") (pin "1") (pinfunction "1_1") (pintype "passive"))
      (node (ref "R32") (pin "1S") (pinfunction "1S_1S") (pintype "passive"))
    )
    (net (code "31") (name "IN4P") (class "Default")
      (node (ref "D10") (pin "3") (pinfunction "AC_3") (pintype "passive"))
      (node (ref "IC4") (pin "13") (pinfunction "-IN_13") (pintype "input"))
      (node (ref "IC4") (pin "9") (pinfunction "-IN_9") (pintype "input"))
      (node (ref "IC6") (pin "11") (pinfunction "S_11") (pintype "bidirectional"))
      (node (ref "IC6") (pin "15") (pinfunction "D_15") (pintype "bidirectional"))
      (node (ref "IC9") (pin "10") (pinfunction "IN4P_10") (pintype "input"))
      (node (ref "JP2") (pin "2") (pinfunction "2_2") (pintype "passive"))
    )
    (net (code "32") (name "ISEL10A_R4_OUT") (class "Default")
      (node (ref "IC2") (pin "11") (pinfunction "8C_11") (pintype "output"))
      (node (ref "ISEL10A_2") (pin "A1") (pinfunction "R_A1") (pintype "passive"))
    )
    (net (code "33") (name "ISEL10A_S4_OUT") (class "Default")
      (node (ref "IC2") (pin "12") (pinfunction "7C_12") (pintype "output"))
      (node (ref "ISEL10A_2") (pin "A2") (pinfunction "S_A2") (pintype "passive"))
    )
    (net (code "34") (name "ISEL10_R#4") (class "Default")
      (node (ref "IC2") (pin "8") (pinfunction "8B_8") (pintype "input"))
      (node (ref "X3") (pin "22") (pinfunction "1_22") (pintype "passive"))
    )
    (net (code "35") (name "ISEL10_S#4") (class "Default")
      (node (ref "IC2") (pin "7") (pinfunction "7B_7") (pintype "input"))
      (node (ref "X3") (pin "20") (pinfunction "1_20") (pintype "passive"))
    )
    (net (code "36") (name "ISEL_LOW#4") (class "Default")
      (node (ref "IC6") (pin "16") (pinfunction "IN_16") (pintype "input"))
      (node (ref "X3") (pin "23") (pinfunction "1_23") (pintype "passive"))
    )
    (net (code "37") (name "ISEL_MID#4") (class "Default")
      (node (ref "IC6") (pin "9") (pinfunction "IN_9") (pintype "input"))
      (node (ref "Q1") (pin "1") (pinfunction "G_1") (pintype "passive"))
      (node (ref "Q2") (pin "1") (pinfunction "G_1") (pintype "passive"))
      (node (ref "X3") (pin "24") (pinfunction "1_24") (pintype "passive"))
    )
    (net (code "38") (name "ISEL_R#2") (class "Default")
      (node (ref "IC2") (pin "4") (pinfunction "4B_4") (pintype "input"))
      (node (ref "X3") (pin "8") (pinfunction "1_8") (pintype "passive"))
    )
    (net (code "39") (name "ISEL_R#4") (class "Default")
      (node (ref "IC2") (pin "6") (pinfunction "6B_6") (pintype "input"))
      (node (ref "X3") (pin "18") (pinfunction "1_18") (pintype "passive"))
    )
    (net (code "40") (name "ISEL_R2_OUT") (class "Default")
      (node (ref "IC2") (pin "15") (pinfunction "4C_15") (pintype "output"))
      (node (ref "ISEL10A_1") (pin "A1") (pinfunction "R_A1") (pintype "passive"))
    )
    (net (code "41") (name "ISEL_R4_OUT") (class "Default")
      (node (ref "IC2") (pin "13") (pinfunction "6C_13") (pintype "output"))
      (node (ref "ISEL1A_1") (pin "7") (pinfunction "R-_7") (pintype "passive"))
    )
    (net (code "42") (name "ISEL_S#2") (class "Default")
      (node (ref "IC2") (pin "3") (pinfunction "3B_3") (pintype "input"))
      (node (ref "X3") (pin "6") (pinfunction "1_6") (pintype "passive"))
    )
    (net (code "43") (name "ISEL_S#4") (class "Default")
      (node (ref "IC2") (pin "5") (pinfunction "5B_5") (pintype "input"))
      (node (ref "X3") (pin "16") (pinfunction "1_16") (pintype "passive"))
    )
    (net (code "44") (name "ISEL_S2_OUT") (class "Default")
      (node (ref "IC2") (pin "16") (pinfunction "3C_16") (pintype "output"))
      (node (ref "ISEL10A_1") (pin "A2") (pinfunction "S_A2") (pintype "passive"))
    )
    (net (code "45") (name "ISEL_S4_OUT") (class "Default")
      (node (ref "IC2") (pin "14") (pinfunction "5C_14") (pintype "output"))
      (node (ref "ISEL1A_1") (pin "12") (pinfunction "S-_12") (pintype "passive"))
    )
    (net (code "46") (name "LO_CLAMP") (class "Default")
      (node (ref "IC4") (pin "12") (pinfunction "+IN_12") (pintype "input"))
      (node (ref "IC4") (pin "3") (pinfunction "+IN_3") (pintype "input"))
      (node (ref "R25") (pin "2") (pinfunction "2_2") (pintype "passive"))
      (node (ref "R26") (pin "1") (pinfunction "1_1") (pintype "passive"))
    )
    (net (code "47") (name "Net-(C27-Pad2)") (class "Default")
      (node (ref "C27") (pin "2") (pinfunction "2_2") (pintype "passive"))
      (node (ref "R33") (pin "1") (pinfunction "1_1") (pintype "passive"))
    )
    (net (code "48") (name "Net-(D1-A)") (class "Default")
      (node (ref "D1") (pin "1") (pinfunction "A_1") (pintype "passive"))
      (node (ref "IC4") (pin "1") (pinfunction "OUT_1") (pintype "output"))
    )
    (net (code "49") (name "Net-(D1-C)") (class "Default")
      (node (ref "D1") (pin "2") (pinfunction "C_2") (pintype "passive"))
      (node (ref "IC4") (pin "7") (pinfunction "OUT_7") (pintype "output"))
    )
    (net (code "50") (name "Net-(D6-A)") (class "Default")
      (node (ref "D6") (pin "2") (pinfunction "A_2") (pintype "passive"))
      (node (ref "D7") (pin "1") (pinfunction "C_1") (pintype "passive"))
      (node (ref "IC6") (pin "14") (pinfunction "S_14") (pintype "bidirectional"))
      (node (ref "ISEL1A_1") (pin "5") (pinfunction "NO_5") (pintype "passive"))
      (node (ref "ISEL1A_1") (pin "8") (pinfunction "NO_8") (pintype "passive"))
      (node (ref "Q1") (pin "2") (pinfunction "S_2") (pintype "passive"))
      (node (ref "R27") (pin "2") (pinfunction "2_2") (pintype "passive"))
      (node (ref "R30") (pin "2") (pinfunction "2_2") (pintype "passive"))
    )
    (net (code "51") (name "Net-(D6-C)") (class "Default")
      (node (ref "D6") (pin "1") (pinfunction "C_1") (pintype "passive"))
      (node (ref "D7") (pin "2") (pinfunction "A_2") (pintype "passive"))
      (node (ref "D8") (pin "1") (pinfunction "C_1") (pintype "passive"))
      (node (ref "D9") (pin "2") (pinfunction "A_2") (pintype "passive"))
      (node (ref "R31") (pin "2") (pinfunction "2_2") (pintype "passive"))
    )
    (net (code "52") (name "Net-(D10-A)") (class "Default")
      (node (ref "D10") (pin "1") (pinfunction "A_1") (pintype "passive"))
      (node (ref "IC4") (pin "14") (pinfunction "OUT_14") (pintype "output"))
    )
    (net (code "53") (name "Net-(D10-C)") (class "Default")
      (node (ref "D10") (pin "2") (pinfunction "C_2") (pintype "passive"))
      (node (ref "IC4") (pin "8") (pinfunction "OUT_8") (pintype "output"))
    )
    (net (code "54") (name "Net-(F2-Pad2)") (class "Default")
      (node (ref "F2") (pin "2") (pinfunction "2_2") (pintype "passive"))
      (node (ref "R8") (pin "2") (pinfunction "2_2") (pintype "passive"))
    )
    (net (code "55") (name "Net-(IC1-DCDC_IN)") (class "Default")
      (node (ref "C3") (pin "1") (pinfunction "1_1") (pintype "passive"))
      (node (ref "IC1") (pin "13") (pinfunction "LDO_OUT_13") (pintype "passive"))
      (node (ref "IC1") (pin "16") (pinfunction "DCDC_IN_16") (pintype "passive"))
    )
    (net (code "56") (name "Net-(IC1-DCDC_OUT)") (class "Default")
      (node (ref "C1") (pin "1") (pinfunction "1_1") (pintype "passive"))
      (node (ref "C2") (pin "1") (pinfunction "1_1") (pintype "passive"))
      (node (ref "C4") (pin "2") (pinfunction "2_2") (pintype "passive"))
      (node (ref "IC1") (pin "1") (pinfunction "DCDC_OUT_1") (pintype "passive"))
      (node (ref "IC1") (pin "3") (pinfunction "HLDO_IN_3") (pintype "passive"))
    )
    (net (code "57") (name "Net-(IC1-HLDO_OUT)") (class "Default")
      (node (ref "C7") (pin "1") (pinfunction "1_1") (pintype "passive"))
      (node (ref "C8") (pin "1") (pinfunction "1_1") (pintype "passive"))
      (node (ref "IC1") (pin "5") (pinfunction "HLDO_OUT_5") (pintype "passive"))
    )
    (net (code "58") (name "Net-(IC1-INP)") (class "Default")
      (node (ref "IC1") (pin "6") (pinfunction "INP_6") (pintype "input"))
      (node (ref "OK1") (pin "4") (pinfunction "S1_4") (pintype "passive"))
      (node (ref "R5") (pin "1") (pinfunction "1_1") (pintype "passive"))
      (node (ref "R7") (pin "2") (pinfunction "2_2") (pintype "passive"))
    )
    (net (code "59") (name "Net-(IC2-COM)") (class "Default")
      (node (ref "IC2") (pin "10") (pinfunction "COM_10") (pintype "passive"))
      (node (ref "ZD1") (pin "C") (pinfunction "C_C") (pintype "passive"))
    )
    (net (code "60") (name "Net-(IC3-DCDC_HGND)") (class "Default")
      (node (ref "C10") (pin "2") (pinfunction "2_2") (pintype "passive"))
      (node (ref "C12") (pin "1") (pinfunction "1_1") (pintype "passive"))
      (node (ref "C15") (pin "2") (pinfunction "2_2") (pintype "passive"))
      (node (ref "C16") (pin "2") (pinfunction "2_2") (pintype "passive"))
      (node (ref "C9") (pin "2") (pinfunction "2_2") (pintype "passive"))
      (node (ref "IC3") (pin "2") (pinfunction "DCDC_HGND_2") (pintype "passive"))
      (node (ref "IC3") (pin "8") (pinfunction "HGND_8") (pintype "passive"))
      (node (ref "L2") (pin "2") (pinfunction "2_2") (pintype "passive"))
      (node (ref "R12") (pin "2") (pinfunction "2_2") (pintype "passive"))
    )
    (net (code "61") (name "Net-(IC3-DCDC_IN)") (class "Default")
      (node (ref "C11") (pin "1") (pinfunction "1_1") (pintype "passive"))
      (node (ref "IC3") (pin "13") (pinfunction "LDO_OUT_13") (pintype "passive"))
      (node (ref "IC3") (pin "16") (pinfunction "DCDC_IN_16") (pintype "passive"))
    )
    (net (code "62") (name "Net-(IC3-DCDC_OUT)") (class "Default")
      (node (ref "C10") (pin "1") (pinfunction "1_1") (pintype "passive"))
      (node (ref "C12") (pin "2") (pinfunction "2_2") (pintype "passive"))
      (node (ref "C9") (pin "1") (pinfunction "1_1") (pintype "passive"))
      (node (ref "IC3") (pin "1") (pinfunction "DCDC_OUT_1") (pintype "passive"))
      (node (ref "IC3") (pin "3") (pinfunction "HLDO_IN_3") (pintype "passive"))
    )
    (net (code "63") (name "Net-(IC3-HLDO_OUT)") (class "Default")
      (node (ref "C15") (pin "1") (pinfunction "1_1") (pintype "passive"))
      (node (ref "C16") (pin "1") (pinfunction "1_1") (pintype "passive"))
      (node (ref "IC3") (pin "5") (pinfunction "HLDO_OUT_5") (pintype "passive"))
    )
    (net (code "64") (name "Net-(IC3-INN)") (class "Default")
      (node (ref "C17") (pin "2") (pinfunction "2_2") (pintype "passive"))
      (node (ref "IC3") (pin "7") (pinfunction "INN_7") (pintype "input"))
      (node (ref "R12") (pin "1") (pinfunction "1_1") (pintype "passive"))
    )
    (net (code "65") (name "Net-(IC3-INP)") (class "Default")
      (node (ref "C17") (pin "1") (pinfunction "1_1") (pintype "passive"))
      (node (ref "IC3") (pin "6") (pinfunction "INP_6") (pintype "input"))
      (node (ref "R10") (pin "1") (pinfunction "1_1") (pintype "passive"))
    )
    (net (code "66") (name "Net-(IC5A-S)") (class "Default")
      (node (ref "IC5") (pin "3") (pinfunction "S_3") (pintype "bidirectional"))
      (node (ref "R19") (pin "1") (pinfunction "1_1") (pintype "passive"))
      (node (ref "R20") (pin "2") (pinfunction "2_2") (pintype "passive"))
    )
    (net (code "67") (name "Net-(IC5B-S)") (class "Default")
      (node (ref "IC5") (pin "14") (pinfunction "S_14") (pintype "bidirectional"))
      (node (ref "R21") (pin "1") (pinfunction "1_1") (pintype "passive"))
      (node (ref "R22") (pin "2") (pinfunction "2_2") (pintype "passive"))
    )
    (net (code "68") (name "Net-(IC5D-S)") (class "Default")
      (node (ref "IC5") (pin "6") (pinfunction "S_6") (pintype "bidirectional"))
      (node (ref "R15") (pin "1") (pinfunction "1_1") (pintype "passive"))
    )
    (net (code "69") (name "Net-(IC6C-D)") (class "Default")
      (node (ref "IC6") (pin "10") (pinfunction "D_10") (pintype "bidirectional"))
      (node (ref "R29") (pin "2S") (pinfunction "2S_2S") (pintype "passive"))
    )
    (net (code "70") (name "Net-(IC7A-+IN)") (class "Default")
      (node (ref "IC7") (pin "3") (pinfunction "+IN_3") (pintype "input"))
      (node (ref "R30") (pin "1") (pinfunction "1_1") (pintype "passive"))
    )
    (net (code "71") (name "Net-(IC7A--IN)") (class "Default")
      (node (ref "IC7") (pin "1") (pinfunction "OUT_1") (pintype "output"))
      (node (ref "IC7") (pin "4") (pinfunction "-IN_4") (pintype "input"))
      (node (ref "R31") (pin "1") (pinfunction "1_1") (pintype "passive"))
    )
    (net (code "72") (name "Net-(IC8-VOUT_F)") (class "Default")
      (node (ref "C27") (pin "1") (pinfunction "1_1") (pintype "passive"))
      (node (ref "C29") (pin "1") (pinfunction "1_1") (pintype "passive"))
      (node (ref "C31") (pin "1") (pinfunction "1_1") (pintype "passive"))
      (node (ref "IC8") (pin "6") (pinfunction "VOUT_S_6") (pintype "output"))
      (node (ref "IC8") (pin "7") (pinfunction "VOUT_F_7") (pintype "output"))
      (node (ref "IC9") (pin "24") (pinfunction "VREFP_24") (pintype "bidirectional"))
    )
    (net (code "73") (name "Net-(IC9-AVDD)") (class "Default")
      (node (ref "C36") (pin "2") (pinfunction "2_2") (pintype "passive"))
      (node (ref "C37") (pin "1") (pinfunction "1_1") (pintype "passive"))
      (node (ref "C38") (pin "1") (pinfunction "1_1") (pintype "passive"))
      (node (ref "C39") (pin "1") (pinfunction "1_1") (pintype "passive"))
      (node (ref "C40") (pin "1") (pinfunction "1_1") (pintype "passive"))
      (node (ref "C41") (pin "2") (pinfunction "2_2") (pintype "passive"))
      (node (ref "IC9") (pin "19") (pinfunction "AVDD_2_19") (pintype "power_in"))
      (node (ref "IC9") (pin "21") (pinfunction "AVDD_3_21") (pintype "power_in"))
      (node (ref "IC9") (pin "22") (pinfunction "AVDD_4_22") (pintype "power_in"))
      (node (ref "IC9") (pin "54") (pinfunction "AVDD1_54") (pintype "power_in"))
      (node (ref "IC9") (pin "56") (pinfunction "AVDD_5_56") (pintype "power_in"))
      (node (ref "IC9") (pin "59") (pinfunction "AVDD_59") (pintype "power_in"))
      (node (ref "R36") (pin "2") (pinfunction "2_2") (pintype "passive"))
    )
    (net (code "74") (name "Net-(IC9-CLK)") (class "Default")
      (node (ref "IC9") (pin "37") (pinfunction "CLK_37") (pintype "input"))
      (node (ref "JP8") (pin "2") (pinfunction "2_2") (pintype "passive"))
    )
    (net (code "75") (name "Net-(IC9-CLKSEL)") (class "Default")
      (node (ref "IC9") (pin "52") (pinfunction "CLKSEL_52") (pintype "input"))
      (node (ref "R35") (pin "1") (pinfunction "1_1") (pintype "passive"))
    )
    (net (code "76") (name "Net-(IC9-VCAP1)") (class "Default")
      (node (ref "C30") (pin "2") (pinfunction "2_2") (pintype "passive"))
      (node (ref "IC9") (pin "28") (pinfunction "VCAP1_28") (pintype "passive"))
    )
    (net (code "77") (name "Net-(IC9-VCAP2)") (class "Default")
      (node (ref "C28") (pin "2") (pinfunction "2_2") (pintype "passive"))
      (node (ref "IC9") (pin "30") (pinfunction "VCAP2_30") (pintype "passive"))
    )
    (net (code "78") (name "Net-(IC9-VCAP3)") (class "Default")
      (node (ref "C25") (pin "2") (pinfunction "2_2") (pintype "passive"))
      (node (ref "C26") (pin "1") (pinfunction "1_1") (pintype "passive"))
      (node (ref "IC9") (pin "55") (pinfunction "VCAP3_55") (pintype "passive"))
    )
    (net (code "79") (name "Net-(IC9-VCAP4)") (class "Default")
      (node (ref "C23") (pin "2") (pinfunction "2_2") (pintype "passive"))
      (node (ref "IC9") (pin "26") (pinfunction "VCAP4_26") (pintype "output"))
    )
    (net (code "80") (name "Net-(IC9-~{PWDN})") (class "Default")
      (node (ref "IC9") (pin "35") (pinfunction "~{PWDN}_35") (pintype "input"))
      (node (ref "R34") (pin "1") (pinfunction "1_1") (pintype "passive"))
    )
    (net (code "81") (name "Net-(IC10-EN)") (class "Default")
      (node (ref "C32") (pin "1") (pinfunction "1_1") (pintype "passive"))
      (node (ref "IC10") (pin "1") (pinfunction "IN_1") (pintype "input"))
      (node (ref "IC10") (pin "3") (pinfunction "EN_3") (pintype "input"))
      (node (ref "L4") (pin "P$1") (pinfunction "1_P$1") (pintype "passive"))
    )
    (net (code "82") (name "Net-(IC11-EN)") (class "Default")
      (node (ref "C33") (pin "1") (pinfunction "1_1") (pintype "passive"))
      (node (ref "IC11") (pin "2") (pinfunction "IN_2") (pintype "input"))
      (node (ref "IC11") (pin "3") (pinfunction "EN_3") (pintype "input"))
      (node (ref "L5") (pin "P$1") (pinfunction "1_P$1") (pintype "passive"))
    )
    (net (code "83") (name "Net-(ISEL1A_1B-COM)") (class "Default")
      (node (ref "F3") (pin "1") (pinfunction "1_1") (pintype "passive"))
      (node (ref "ISEL1A_1") (pin "4") (pinfunction "COM_4") (pintype "passive"))
      (node (ref "ISEL1A_1") (pin "9") (pinfunction "COM_9") (pintype "passive"))
    )
    (net (code "84") (name "Net-(ISEL10A_1B-COM)") (class "Default")
      (node (ref "F1") (pin "1") (pinfunction "1_1") (pintype "passive"))
      (node (ref "F2") (pin "1") (pinfunction "1_1") (pintype "passive"))
      (node (ref "ISEL10A_1") (pin "11") (pinfunction "COM_11") (pintype "passive"))
    )
    (net (code "85") (name "Net-(ISEL10A_1B-NC)") (class "Default")
      (node (ref "ISEL10A_1") (pin "12") (pinfunction "NC_12") (pintype "passive"))
      (node (ref "R11") (pin "2") (pinfunction "2_2") (pintype "passive"))
      (node (ref "R8") (pin "1") (pinfunction "1_1") (pintype "passive"))
      (node (ref "R8") (pin "1S") (pinfunction "1S_1S") (pintype "passive"))
    )
    (net (code "86") (name "Net-(ISEL10A_1C-COM)") (class "Default")
      (node (ref "ISEL10A_1") (pin "21") (pinfunction "COM_21") (pintype "passive"))
      (node (ref "L2") (pin "4") (pinfunction "4_4") (pintype "passive"))
    )
    (net (code "87") (name "Net-(ISEL10A_1C-NC)") (class "Default")
      (node (ref "ISEL10A_1") (pin "22") (pinfunction "NC_22") (pintype "passive"))
      (node (ref "R11") (pin "2S") (pinfunction "2S_2S") (pintype "passive"))
    )
    (net (code "88") (name "Net-(ISEL10A_1C-NO)") (class "Default")
      (node (ref "ISEL10A_1") (pin "24") (pinfunction "NO_24") (pintype "passive"))
      (node (ref "R8") (pin "2S") (pinfunction "2S_2S") (pintype "passive"))
    )
    (net (code "89") (name "Net-(ISEL10A_2B-COM)") (class "Default")
      (node (ref "F4") (pin "1") (pinfunction "1_1") (pintype "passive"))
      (node (ref "ISEL10A_2") (pin "11") (pinfunction "COM_11") (pintype "passive"))
      (node (ref "ISEL10A_2") (pin "21") (pinfunction "COM_21") (pintype "passive"))
    )
    (net (code "90") (name "Net-(ISEL10A_2B-NC)") (class "Default")
      (node (ref "ISEL10A_2") (pin "12") (pinfunction "NC_12") (pintype "passive"))
      (node (ref "ISEL10A_2") (pin "22") (pinfunction "NC_22") (pintype "passive"))
      (node (ref "R32") (pin "2") (pinfunction "2_2") (pintype "passive"))
    )
    (net (code "91") (name "Net-(JP7-PadCOM)") (class "Default")
      (node (ref "JP7") (pin "COM") (pinfunction "COM_COM") (pintype "passive"))
      (node (ref "R35") (pin "2") (pinfunction "2_2") (pintype "passive"))
    )
    (net (code "92") (name "Net-(L1-1)") (class "Default")
      (node (ref "L1") (pin "P$1") (pinfunction "1_P$1") (pintype "passive"))
      (node (ref "R1") (pin "2") (pinfunction "2_2") (pintype "passive"))
    )
    (net (code "93") (name "Net-(L2-Pad1)") (class "Default")
      (node (ref "L2") (pin "1") (pinfunction "1_1") (pintype "passive"))
      (node (ref "R11") (pin "1S") (pinfunction "1S_1S") (pintype "passive"))
    )
    (net (code "94") (name "Net-(L2-Pad3)") (class "Default")
      (node (ref "L2") (pin "3") (pinfunction "3_3") (pintype "passive"))
      (node (ref "R10") (pin "2") (pinfunction "2_2") (pintype "passive"))
    )
    (net (code "95") (name "Net-(L3-2)") (class "Default")
      (node (ref "L3") (pin "P$2") (pinfunction "2_P$2") (pintype "passive"))
      (node (ref "X1") (pin "5") (pinfunction "1_5") (pintype "passive"))
    )
    (net (code "96") (name "Net-(OK1-A)") (class "Default")
      (node (ref "OK1") (pin "1") (pinfunction "A_1") (pintype "passive"))
      (node (ref "R2") (pin "1") (pinfunction "1_1") (pintype "passive"))
    )
    (net (code "97") (name "Net-(OK1-S2)") (class "Default")
      (node (ref "OK1") (pin "3") (pinfunction "S2_3") (pintype "passive"))
      (node (ref "R6") (pin "2") (pinfunction "2_2") (pintype "passive"))
    )
    (net (code "98") (name "Net-(OK2-A)") (class "Default")
      (node (ref "OK2") (pin "1") (pinfunction "A_1") (pintype "passive"))
      (node (ref "R13") (pin "2") (pinfunction "2_2") (pintype "passive"))
    )
    (net (code "99") (name "Net-(OK2-S1)") (class "Default")
      (node (ref "OK2") (pin "4") (pinfunction "S1_4") (pintype "passive"))
      (node (ref "R14") (pin "2") (pinfunction "2_2") (pintype "passive"))
    )
    (net (code "100") (name "Net-(Q1-D)") (class "Default")
      (node (ref "Q1") (pin "3") (pinfunction "D_3") (pintype "passive"))
      (node (ref "Q2") (pin "3") (pinfunction "D_3") (pintype "passive"))
    )
    (net (code "101") (name "Net-(Q2-S)") (class "Default")
      (node (ref "Q2") (pin "2") (pinfunction "S_2") (pintype "passive"))
      (node (ref "R27") (pin "1") (pinfunction "1_1") (pintype "passive"))
      (node (ref "R29") (pin "2") (pinfunction "2_2") (pintype "passive"))
    )
    (net (code "102") (name "Net-(R1-Pad1)") (class "Default")
      (node (ref "R1") (pin "1") (pinfunction "1_1") (pintype "passive"))
      (node (ref "R3") (pin "2") (pinfunction "2_2") (pintype "passive"))
    )
    (net (code "103") (name "Net-(R3-Pad1)") (class "Default")
      (node (ref "R3") (pin "1") (pinfunction "1_1") (pintype "passive"))
      (node (ref "R5") (pin "2") (pinfunction "2_2") (pintype "passive"))
    )
    (net (code "104") (name "Net-(R14-Pad1)") (class "Default")
      (node (ref "R14") (pin "1") (pinfunction "1_1") (pintype "passive"))
      (node (ref "R15") (pin "2") (pinfunction "2_2") (pintype "passive"))
    )
    (net (code "105") (name "Net-(R17-Pad1)") (class "Default")
      (node (ref "R17") (pin "1") (pinfunction "1_1") (pintype "passive"))
      (node (ref "R18") (pin "2") (pinfunction "2_2") (pintype "passive"))
    )
    (net (code "106") (name "Net-(R18-Pad1)") (class "Default")
      (node (ref "R18") (pin "1") (pinfunction "1_1") (pintype "passive"))
      (node (ref "R19") (pin "2") (pinfunction "2_2") (pintype "passive"))
    )
    (net (code "107") (name "Net-(R20-Pad1)") (class "Default")
      (node (ref "R20") (pin "1") (pinfunction "1_1") (pintype "passive"))
      (node (ref "R21") (pin "2") (pinfunction "2_2") (pintype "passive"))
    )
    (net (code "108") (name "Net-(R29-Pad1)") (class "Default")
      (node (ref "R29") (pin "1") (pinfunction "1_1") (pintype "passive"))
      (node (ref "R29") (pin "1S") (pinfunction "1S_1S") (pintype "passive"))
      (node (ref "R32") (pin "2S") (pinfunction "2S_2S") (pintype "passive"))
    )
    (net (code "109") (name "Net-(X1C-1)") (class "Default")
      (node (ref "F1") (pin "2") (pinfunction "2_2") (pintype "passive"))
      (node (ref "X1") (pin "3") (pinfunction "1_3") (pintype "passive"))
    )
    (net (code "110") (name "Net-(X1D-1)") (class "Default")
      (node (ref "R11") (pin "1") (pinfunction "1_1") (pintype "passive"))
      (node (ref "X1") (pin "4") (pinfunction "1_4") (pintype "passive"))
    )
    (net (code "111") (name "Net-(X2P-1)") (class "Default")
      (node (ref "JP1") (pin "2") (pinfunction "2_2") (pintype "passive"))
      (node (ref "X2") (pin "23") (pinfunction "1_23") (pintype "passive"))
    )
    (net (code "112") (name "Net-(X2Q-1)") (class "Default")
      (node (ref "JP2") (pin "1") (pinfunction "1_1") (pintype "passive"))
      (node (ref "X2") (pin "24") (pinfunction "1_24") (pintype "passive"))
    )
    (net (code "113") (name "Net-(X2R-1)") (class "Default")
      (node (ref "JP3") (pin "2") (pinfunction "2_2") (pintype "passive"))
      (node (ref "X2") (pin "25") (pinfunction "1_25") (pintype "passive"))
    )
    (net (code "114") (name "Net-(X2S-1)") (class "Default")
      (node (ref "JP4") (pin "1") (pinfunction "1_1") (pintype "passive"))
      (node (ref "X2") (pin "26") (pinfunction "1_26") (pintype "passive"))
    )
    (net (code "115") (name "USEL#1") (class "Default")
      (node (ref "R2") (pin "2") (pinfunction "2_2") (pintype "passive"))
      (node (ref "X3") (pin "5") (pinfunction "1_5") (pintype "passive"))
    )
    (net (code "116") (name "USEL1#3") (class "Default")
      (node (ref "IC5") (pin "8") (pinfunction "IN_8") (pintype "input"))
      (node (ref "R13") (pin "1") (pinfunction "1_1") (pintype "passive"))
      (node (ref "X3") (pin "11") (pinfunction "1_11") (pintype "passive"))
    )
    (net (code "117") (name "USEL20#3") (class "Default")
      (node (ref "IC5") (pin "1") (pinfunction "IN_1") (pintype "input"))
      (node (ref "X3") (pin "13") (pinfunction "1_13") (pintype "passive"))
    )
    (net (code "118") (name "USEL100#3") (class "Default")
      (node (ref "IC5") (pin "16") (pinfunction "IN_16") (pintype "input"))
      (node (ref "X3") (pin "9") (pinfunction "1_9") (pintype "passive"))
    )
    (net (code "119") (name "unconnected-(IC2-1B-Pad1)") (class "Default")
      (node (ref "IC2") (pin "1") (pinfunction "1B_1") (pintype "input"))
    )
    (net (code "120") (name "unconnected-(IC2-1C-Pad18)") (class "Default")
      (node (ref "IC2") (pin "18") (pinfunction "1C_18") (pintype "output"))
    )
    (net (code "121") (name "unconnected-(IC2-2B-Pad2)") (class "Default")
      (node (ref "IC2") (pin "2") (pinfunction "2B_2") (pintype "input"))
    )
    (net (code "122") (name "unconnected-(IC2-2C-Pad17)") (class "Default")
      (node (ref "IC2") (pin "17") (pinfunction "2C_17") (pintype "output"))
    )
    (net (code "123") (name "unconnected-(IC9-GPIO1-Pad42)") (class "Default")
      (node (ref "IC9") (pin "42") (pinfunction "GPIO1_42") (pintype "bidirectional"))
    )
    (net (code "124") (name "unconnected-(IC9-GPIO2-Pad44)") (class "Default")
      (node (ref "IC9") (pin "44") (pinfunction "GPIO2_44") (pintype "bidirectional"))
    )
    (net (code "125") (name "unconnected-(IC9-GPIO3-Pad45)") (class "Default")
      (node (ref "IC9") (pin "45") (pinfunction "GPIO3_45") (pintype "bidirectional"))
    )
    (net (code "126") (name "unconnected-(IC9-GPIO4-Pad46)") (class "Default")
      (node (ref "IC9") (pin "46") (pinfunction "GPIO4_46") (pintype "bidirectional"))
    )
    (net (code "127") (name "unconnected-(IC9-IN5N(NC)-Pad7)") (class "Default")
      (node (ref "IC9") (pin "7") (pinfunction "IN5N(NC)_7") (pintype "input"))
    )
    (net (code "128") (name "unconnected-(IC9-IN5P(NC)-Pad8)") (class "Default")
      (node (ref "IC9") (pin "8") (pinfunction "IN5P(NC)_8") (pintype "input"))
    )
    (net (code "129") (name "unconnected-(IC9-IN6N(NC)-Pad5)") (class "Default")
      (node (ref "IC9") (pin "5") (pinfunction "IN6N(NC)_5") (pintype "input"))
    )
    (net (code "130") (name "unconnected-(IC9-IN6P(NC)-Pad6)") (class "Default")
      (node (ref "IC9") (pin "6") (pinfunction "IN6P(NC)_6") (pintype "input"))
    )
    (net (code "131") (name "unconnected-(IC9-IN7N(NC)-Pad3)") (class "Default")
      (node (ref "IC9") (pin "3") (pinfunction "IN7N(NC)_3") (pintype "input"))
    )
    (net (code "132") (name "unconnected-(IC9-IN7P(NC)-Pad4)") (class "Default")
      (node (ref "IC9") (pin "4") (pinfunction "IN7P(NC)_4") (pintype "input"))
    )
    (net (code "133") (name "unconnected-(IC9-IN8N(NC)-Pad1)") (class "Default")
      (node (ref "IC9") (pin "1") (pinfunction "IN8N(NC)_1") (pintype "input"))
    )
    (net (code "134") (name "unconnected-(IC9-IN8P(NC)-Pad2)") (class "Default")
      (node (ref "IC9") (pin "2") (pinfunction "IN8P(NC)_2") (pintype "input"))
    )
    (net (code "135") (name "unconnected-(IC9-OPAMPN-Pad61)") (class "Default")
      (node (ref "IC9") (pin "61") (pinfunction "OPAMPN_61") (pintype "input"))
    )
    (net (code "136") (name "unconnected-(IC9-OPAMPOUT-Pad63)") (class "Default")
      (node (ref "IC9") (pin "63") (pinfunction "OPAMPOUT_63") (pintype "output"))
    )
    (net (code "137") (name "unconnected-(IC9-OPAMPP-Pad60)") (class "Default")
      (node (ref "IC9") (pin "60") (pinfunction "OPAMPP_60") (pintype "input"))
    )
    (net (code "138") (name "unconnected-(IC9-TESTN-Pad18)") (class "Default")
      (node (ref "IC9") (pin "18") (pinfunction "TESTN_18") (pintype "bidirectional"))
    )
    (net (code "139") (name "unconnected-(IC9-TESTP-Pad17)") (class "Default")
      (node (ref "IC9") (pin "17") (pinfunction "TESTP_17") (pintype "bidirectional"))
    )
    (net (code "140") (name "unconnected-(IC10-NR-Pad4)") (class "Default")
      (node (ref "IC10") (pin "4") (pinfunction "NR_4") (pintype "passive"))
    )
    (net (code "141") (name "unconnected-(IC11-NR-Pad4)") (class "Default")
      (node (ref "IC11") (pin "4") (pinfunction "NR_4") (pintype "passive"))
    )
    (net (code "142") (name "unconnected-(ISEL1A_1B-NC-Pad3)") (class "Default")
      (node (ref "ISEL1A_1") (pin "3") (pinfunction "NC_3") (pintype "passive"))
    )
    (net (code "143") (name "unconnected-(ISEL1A_1C-NC-Pad10)") (class "Default")
      (node (ref "ISEL1A_1") (pin "10") (pinfunction "NC_10") (pintype "passive"))
    )
    (net (code "144") (name "unconnected-(ISEL10A_1B-NO-Pad14)") (class "Default")
      (node (ref "ISEL10A_1") (pin "14") (pinfunction "NO_14") (pintype "passive"))
    )
    (net (code "145") (name "unconnected-(ISEL10A_2B-NO-Pad14)") (class "Default")
      (node (ref "ISEL10A_2") (pin "14") (pinfunction "NO_14") (pintype "passive"))
    )
    (net (code "146") (name "unconnected-(ISEL10A_2C-NO-Pad24)") (class "Default")
      (node (ref "ISEL10A_2") (pin "24") (pinfunction "NO_24") (pintype "passive"))
    )
    (net (code "147") (name "unconnected-(X2I-1-Pad17)") (class "Default")
      (node (ref "X2") (pin "17") (pinfunction "1_17") (pintype "passive"))
    )
    (net (code "148") (name "unconnected-(X2J-1-Pad18)") (class "Default")
      (node (ref "X2") (pin "18") (pinfunction "1_18") (pintype "passive"))
    )
    (net (code "149") (name "unconnected-(X3B-1-Pad10)") (class "Default")
      (node (ref "X3") (pin "10") (pinfunction "1_10") (pintype "passive"))
    )
    (net (code "150") (name "unconnected-(X3D-1-Pad12)") (class "Default")
      (node (ref "X3") (pin "12") (pinfunction "1_12") (pintype "passive"))
    )
    (net (code "151") (name "unconnected-(X3F-1-Pad14)") (class "Default")
      (node (ref "X3") (pin "14") (pinfunction "1_14") (pintype "passive"))
    )
    (net (code "152") (name "unconnected-(X3G-1-Pad15)") (class "Default")
      (node (ref "X3") (pin "15") (pinfunction "1_15") (pintype "passive"))
    )
    (net (code "153") (name "unconnected-(X3I-1-Pad17)") (class "Default")
      (node (ref "X3") (pin "17") (pinfunction "1_17") (pintype "passive"))
    )
    (net (code "154") (name "unconnected-(X3K-1-Pad19)") (class "Default")
      (node (ref "X3") (pin "19") (pinfunction "1_19") (pintype "passive"))
    )
    (net (code "155") (name "unconnected-(X3L-1-Pad2)") (class "Default")
      (node (ref "X3") (pin "2") (pinfunction "1_2") (pintype "passive"))
    )
    (net (code "156") (name "unconnected-(X3N-1-Pad21)") (class "Default")
      (node (ref "X3") (pin "21") (pinfunction "1_21") (pintype "passive"))
    )
    (net (code "157") (name "unconnected-(X3R-1-Pad25)") (class "Default")
      (node (ref "X3") (pin "25") (pinfunction "1_25") (pintype "passive"))
    )
    (net (code "158") (name "unconnected-(X3S-1-Pad26)") (class "Default")
      (node (ref "X3") (pin "26") (pinfunction "1_26") (pintype "passive"))
    )
    (net (code "159") (name "unconnected-(X3Z-1-Pad7)") (class "Default")
      (node (ref "X3") (pin "7") (pinfunction "1_7") (pintype "passive"))
    )
    (net (code "160") (name "~{ADC_CS}") (class "Default")
      (node (ref "IC9") (pin "39") (pinfunction "~{CS}_39") (pintype "input"))
      (node (ref "X2") (pin "5") (pinfunction "1_5") (pintype "passive"))
    )
    (net (code "161") (name "~{ADC_DRDY}") (class "Default")
      (node (ref "IC9") (pin "47") (pinfunction "~{DRDY}_47") (pintype "output"))
      (node (ref "X2") (pin "7") (pinfunction "1_7") (pintype "passive"))
    )
    (net (code "162") (name "~{RESET}") (class "Default")
      (node (ref "IC9") (pin "36") (pinfunction "~{RESET}_36") (pintype "input"))
      (node (ref "X2") (pin "9") (pinfunction "1_9") (pintype "passive"))
    )
  )
)
